# MAIN_CNTRL_v02.net
KiCad netlist of a schematic drawn in EAGLE
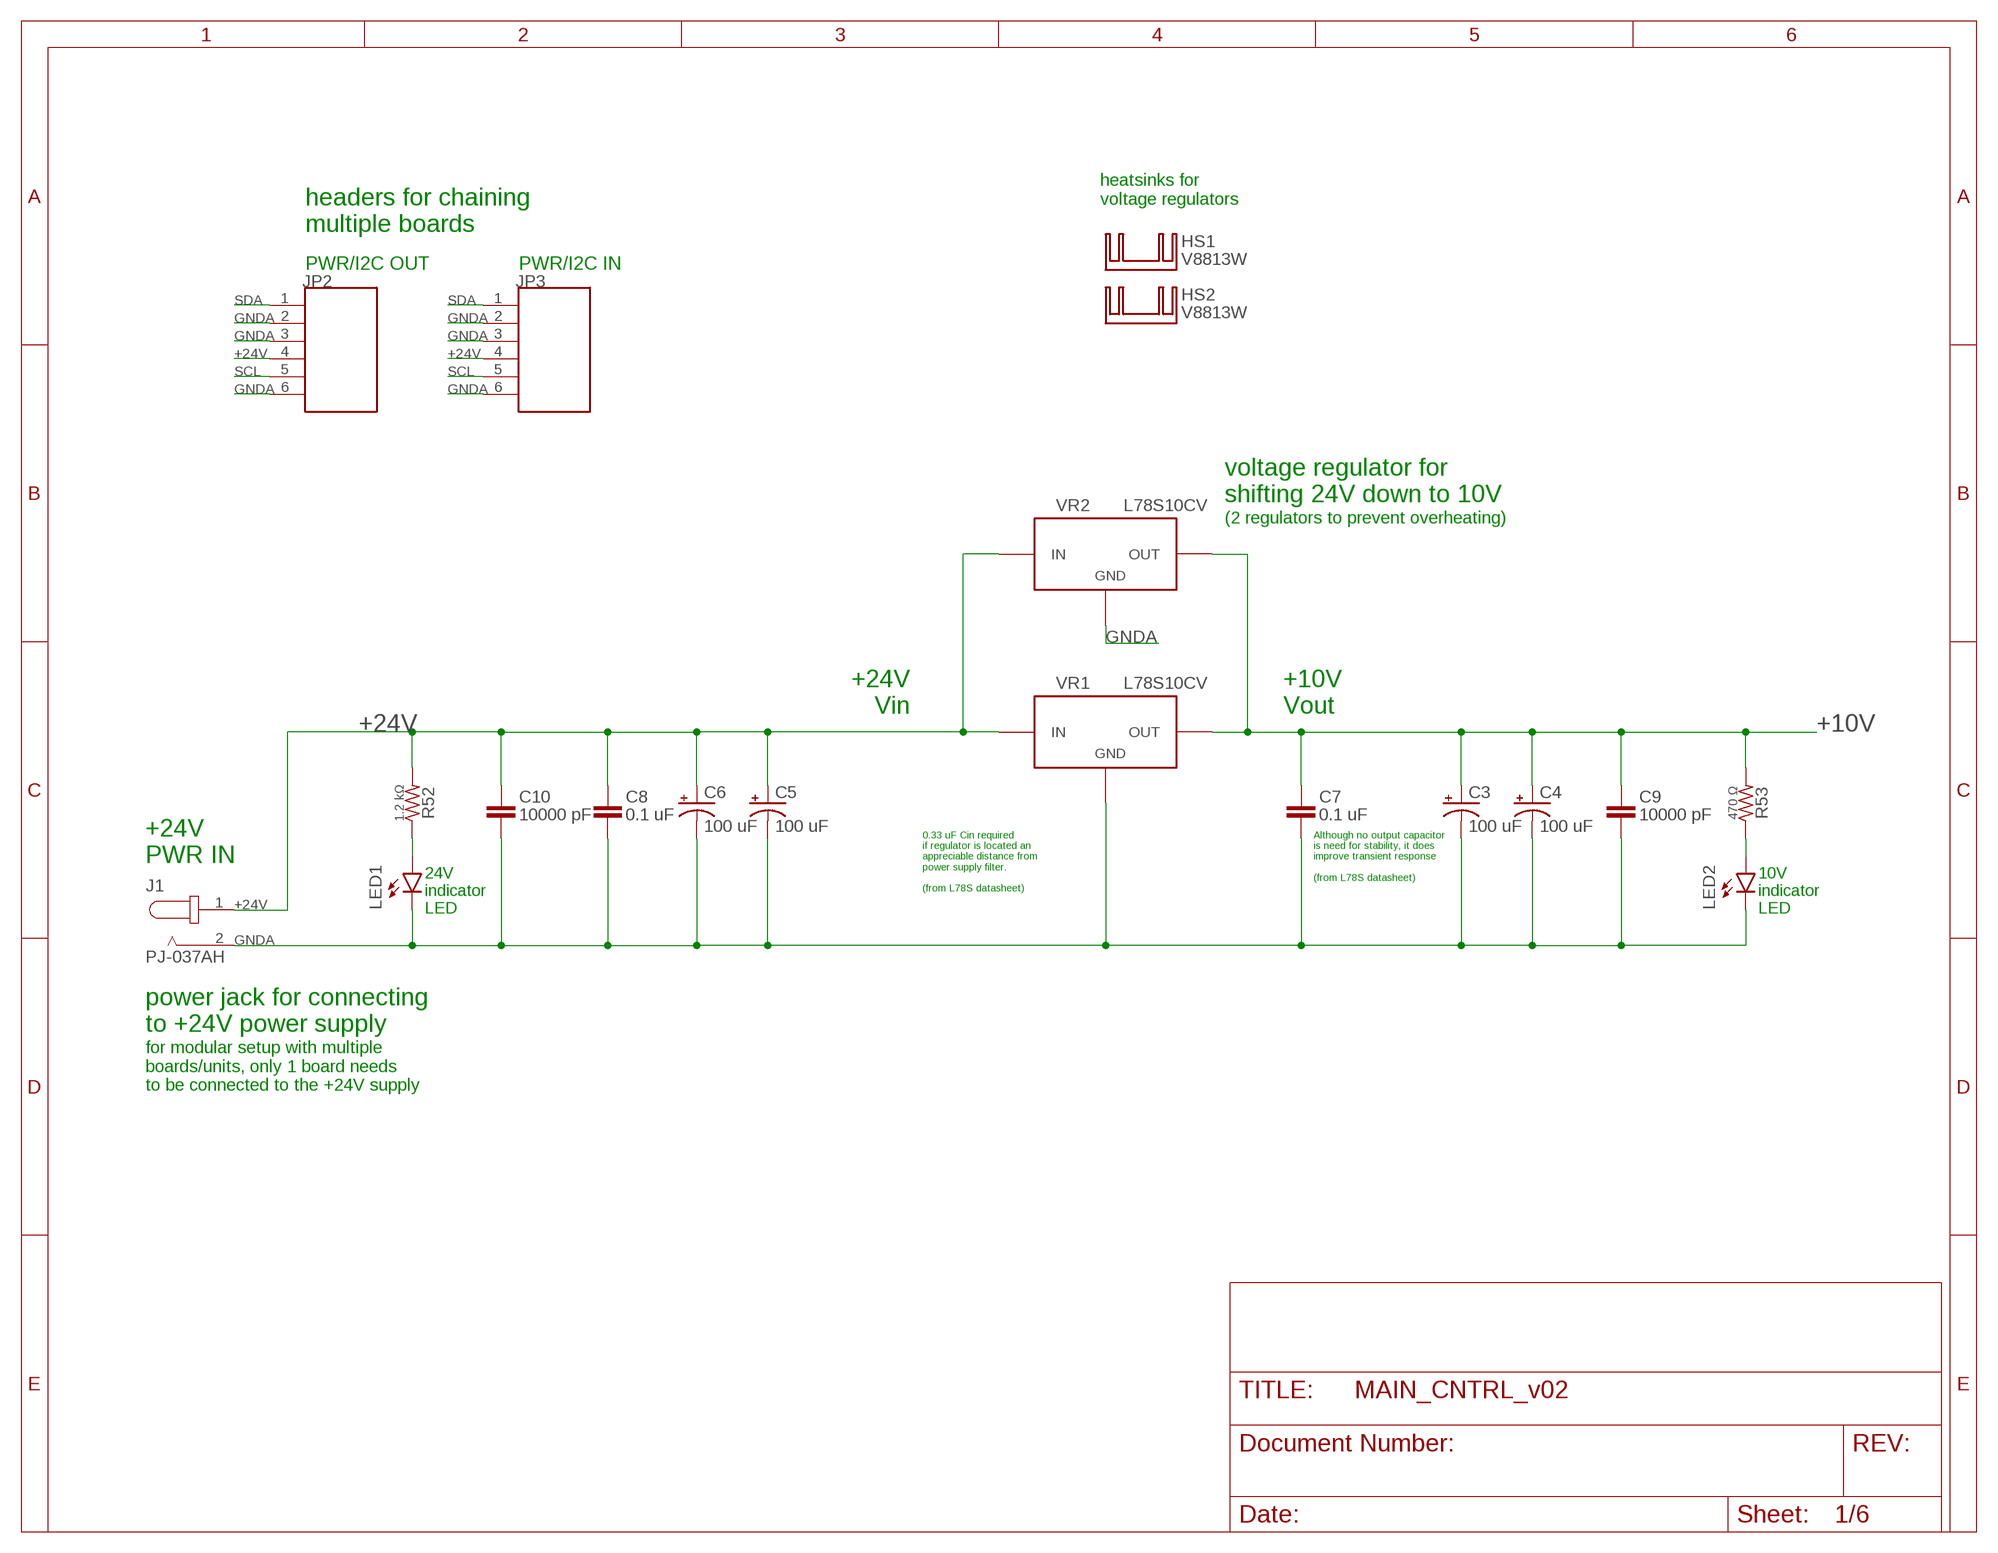
[diagram p0: schematic, sheet 1]
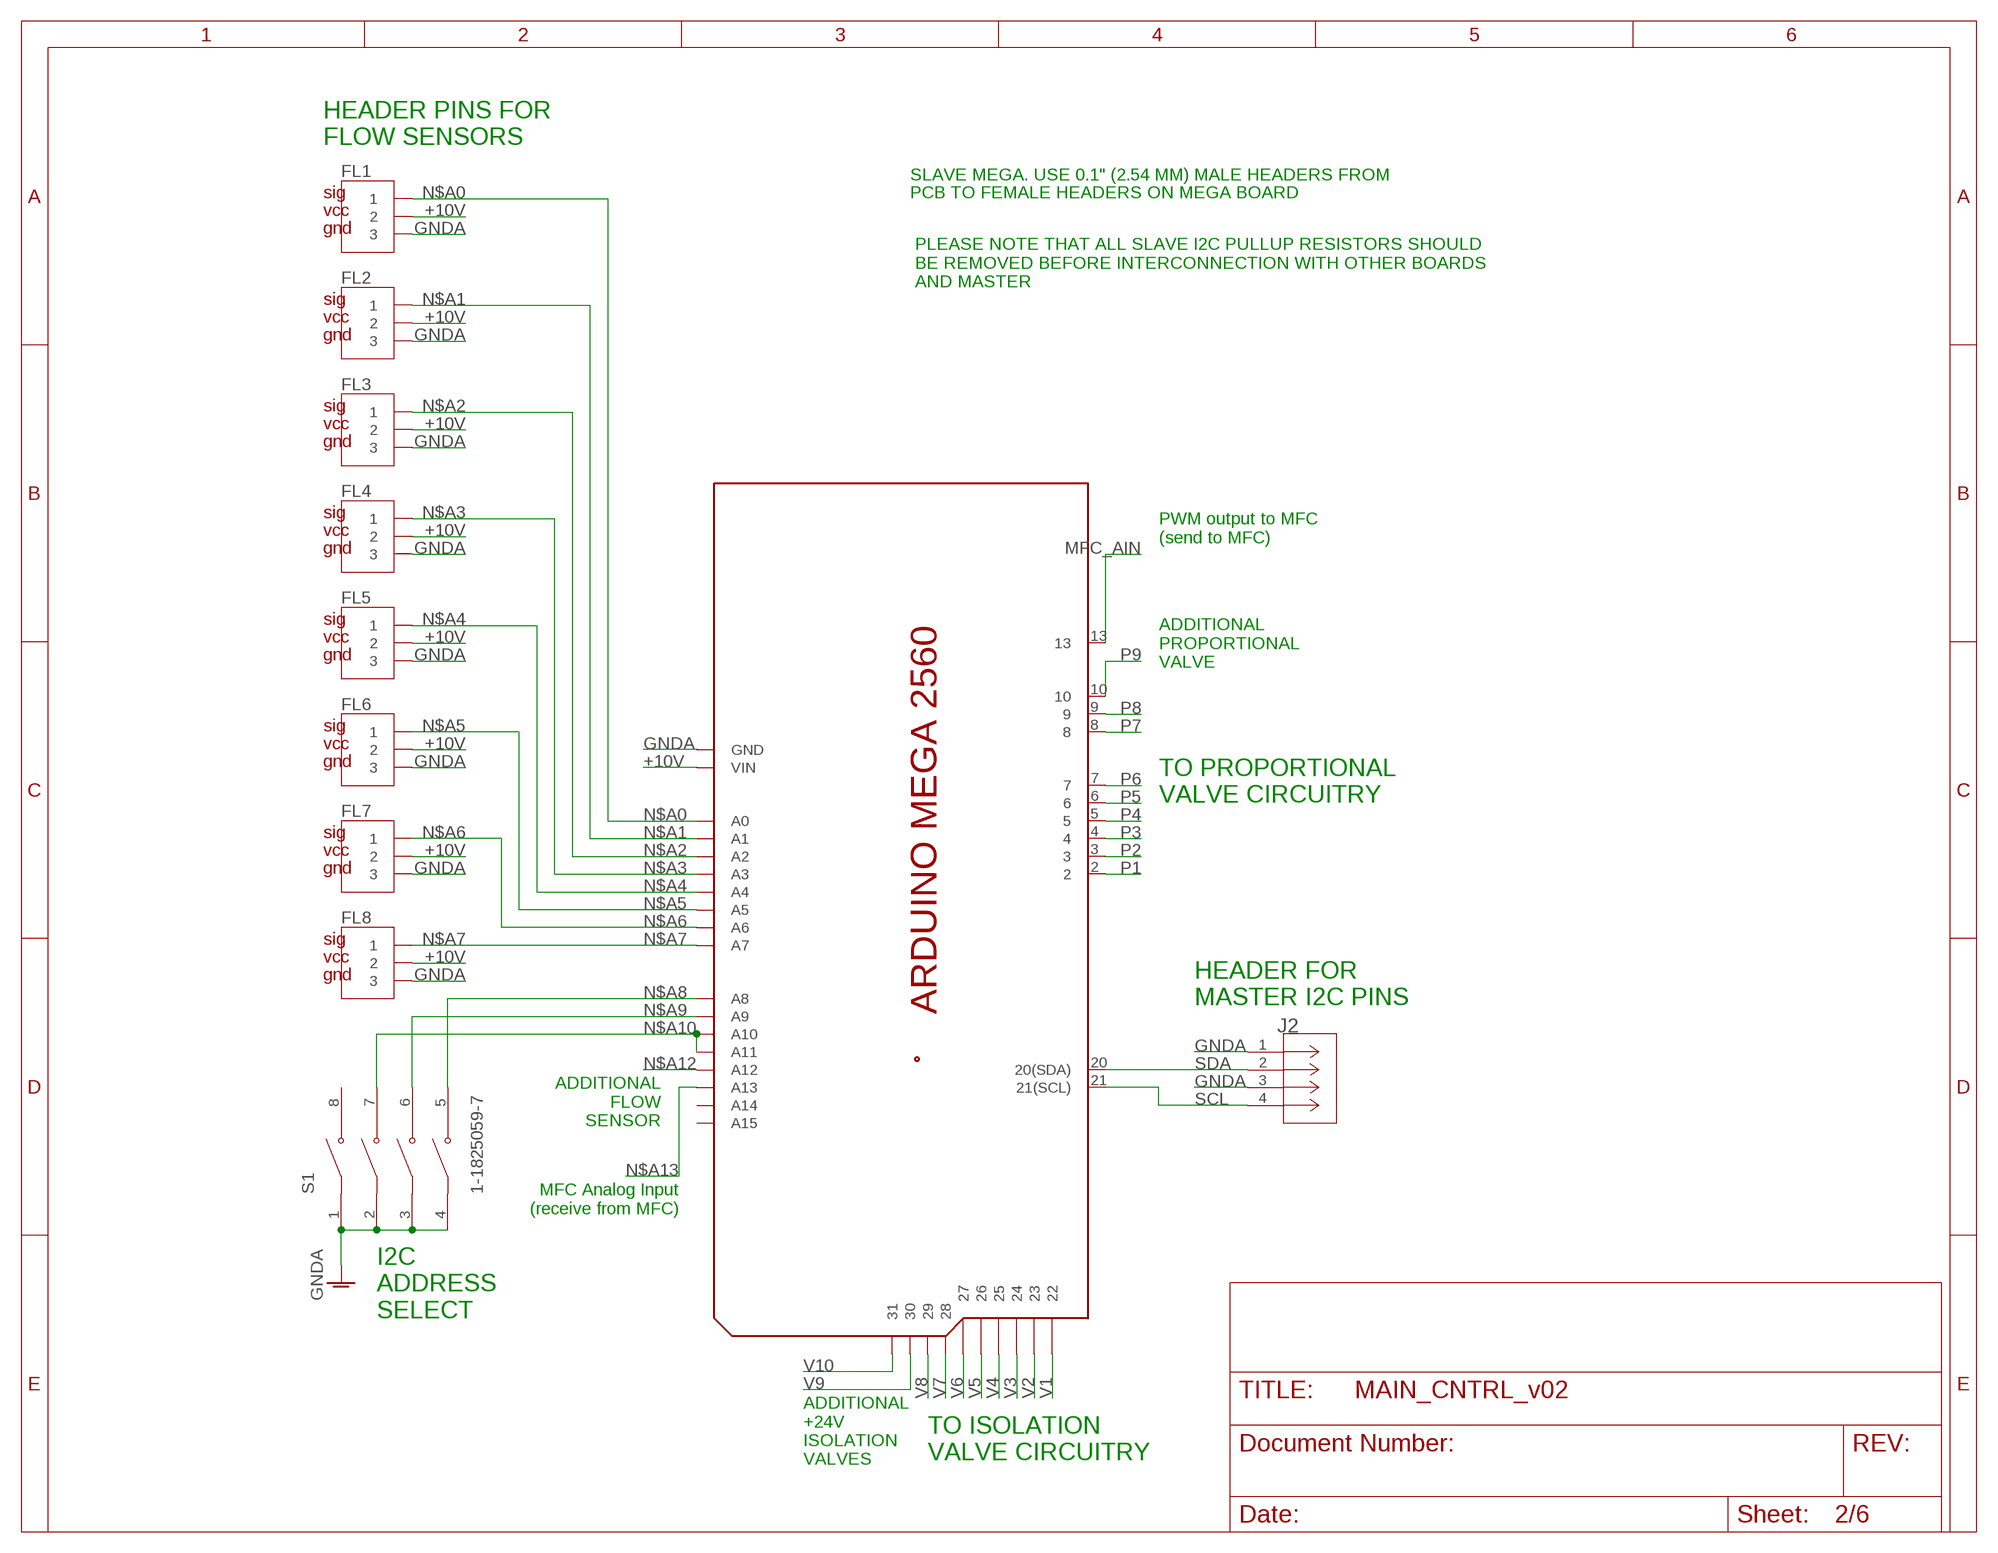
[diagram p1: schematic, sheet 2]
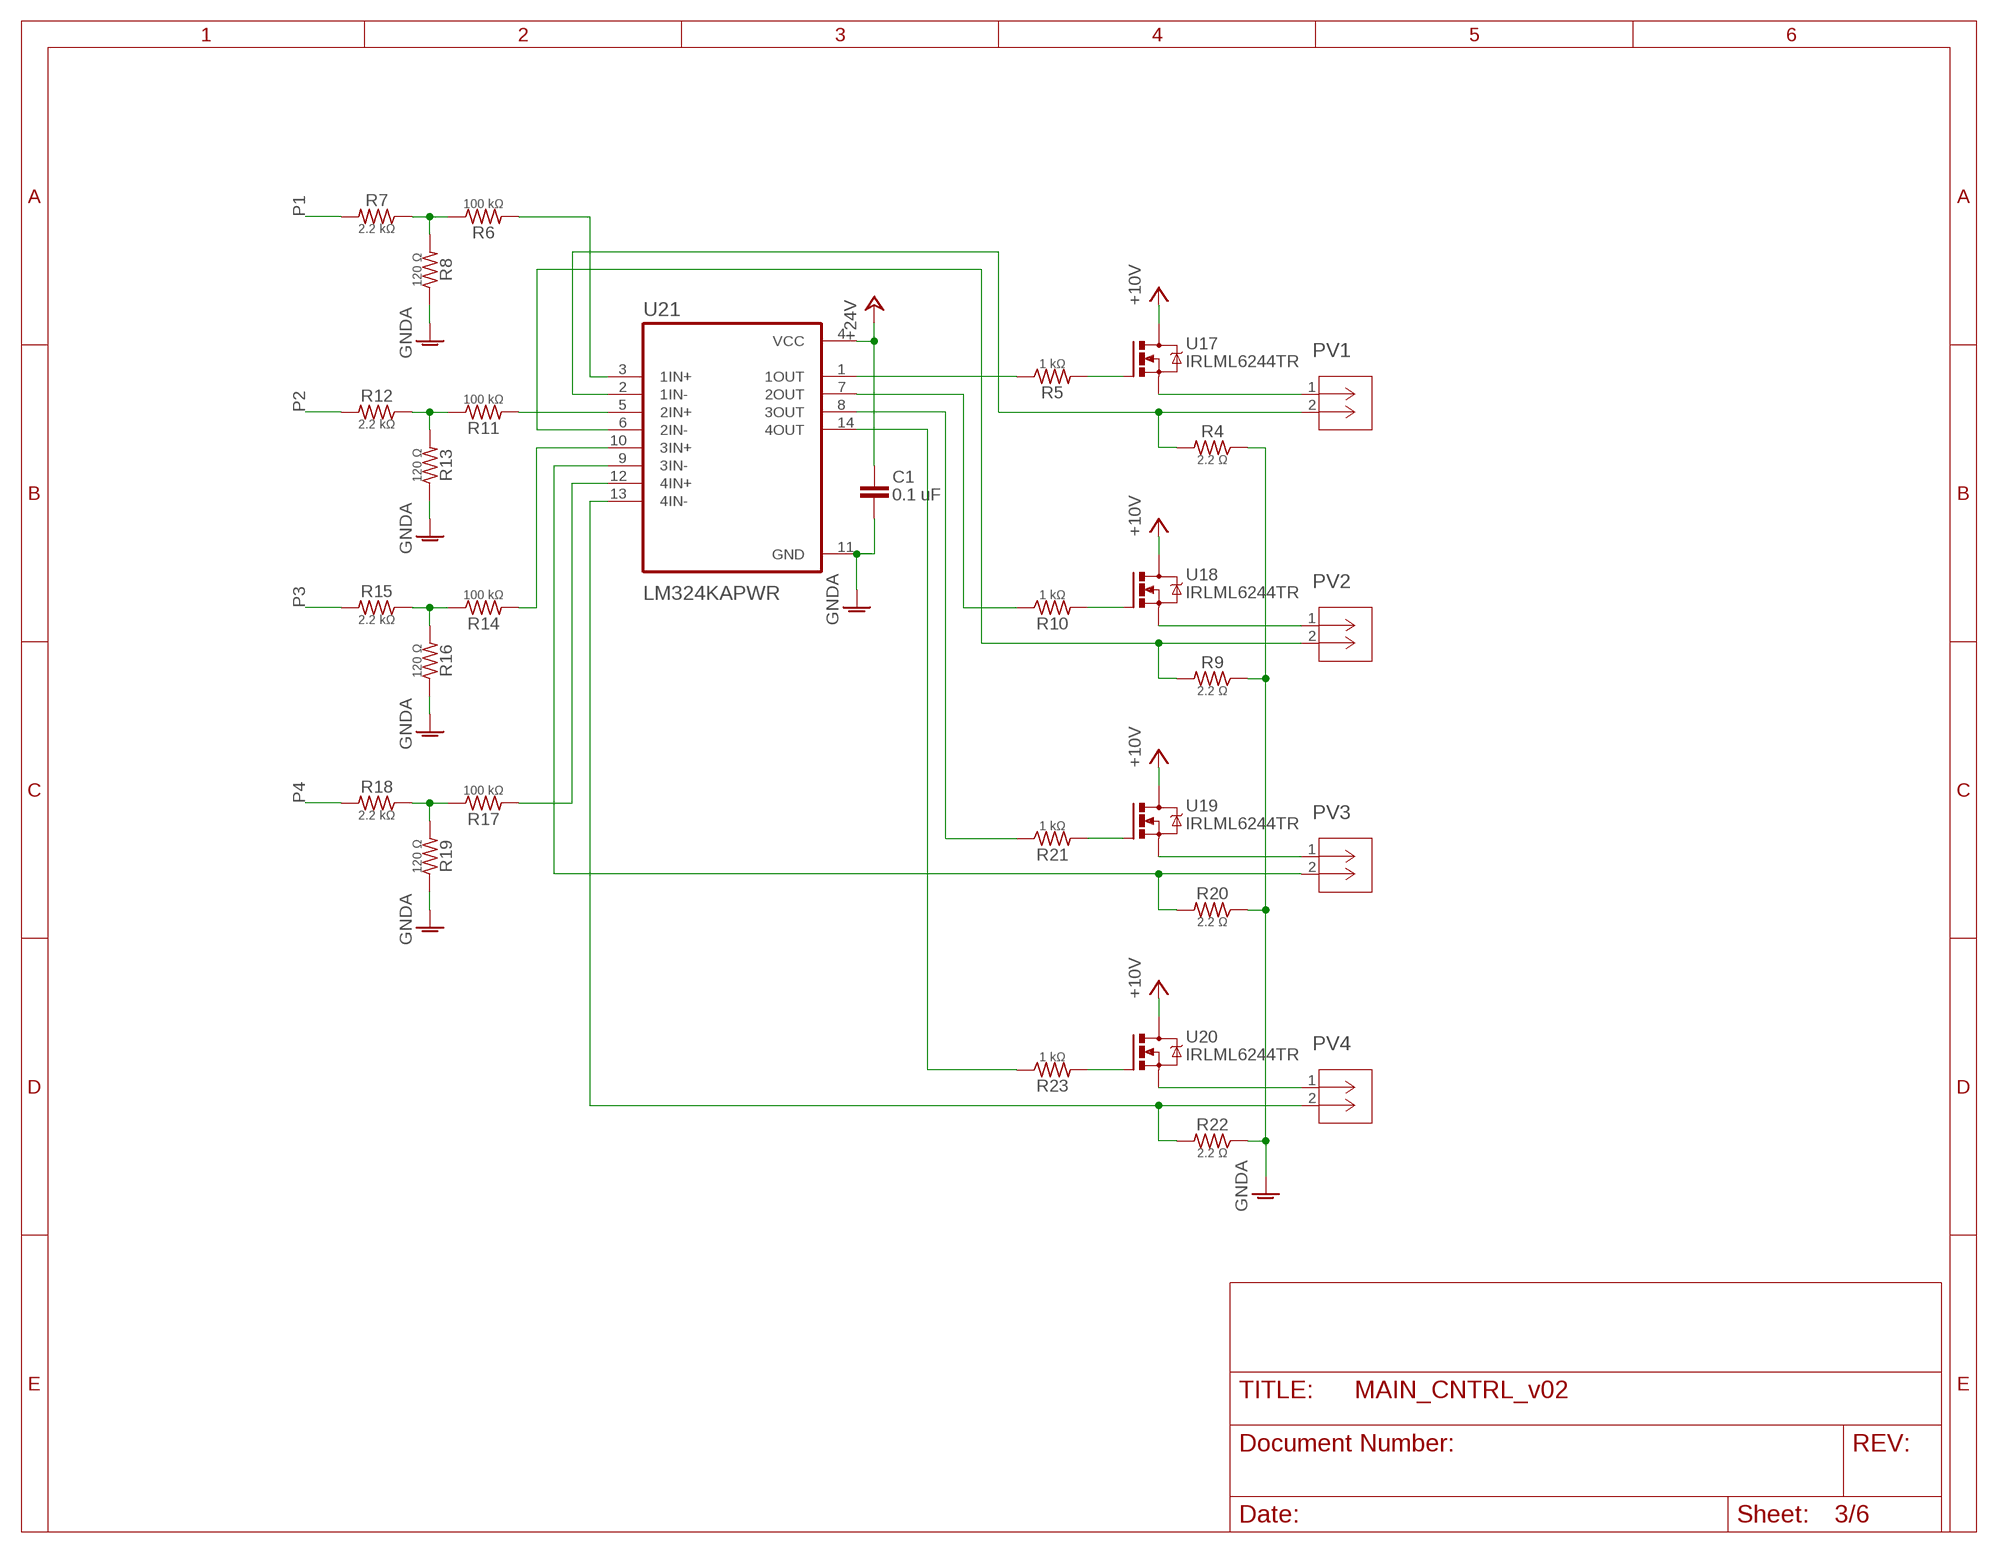
[diagram p2: schematic, sheet 3]
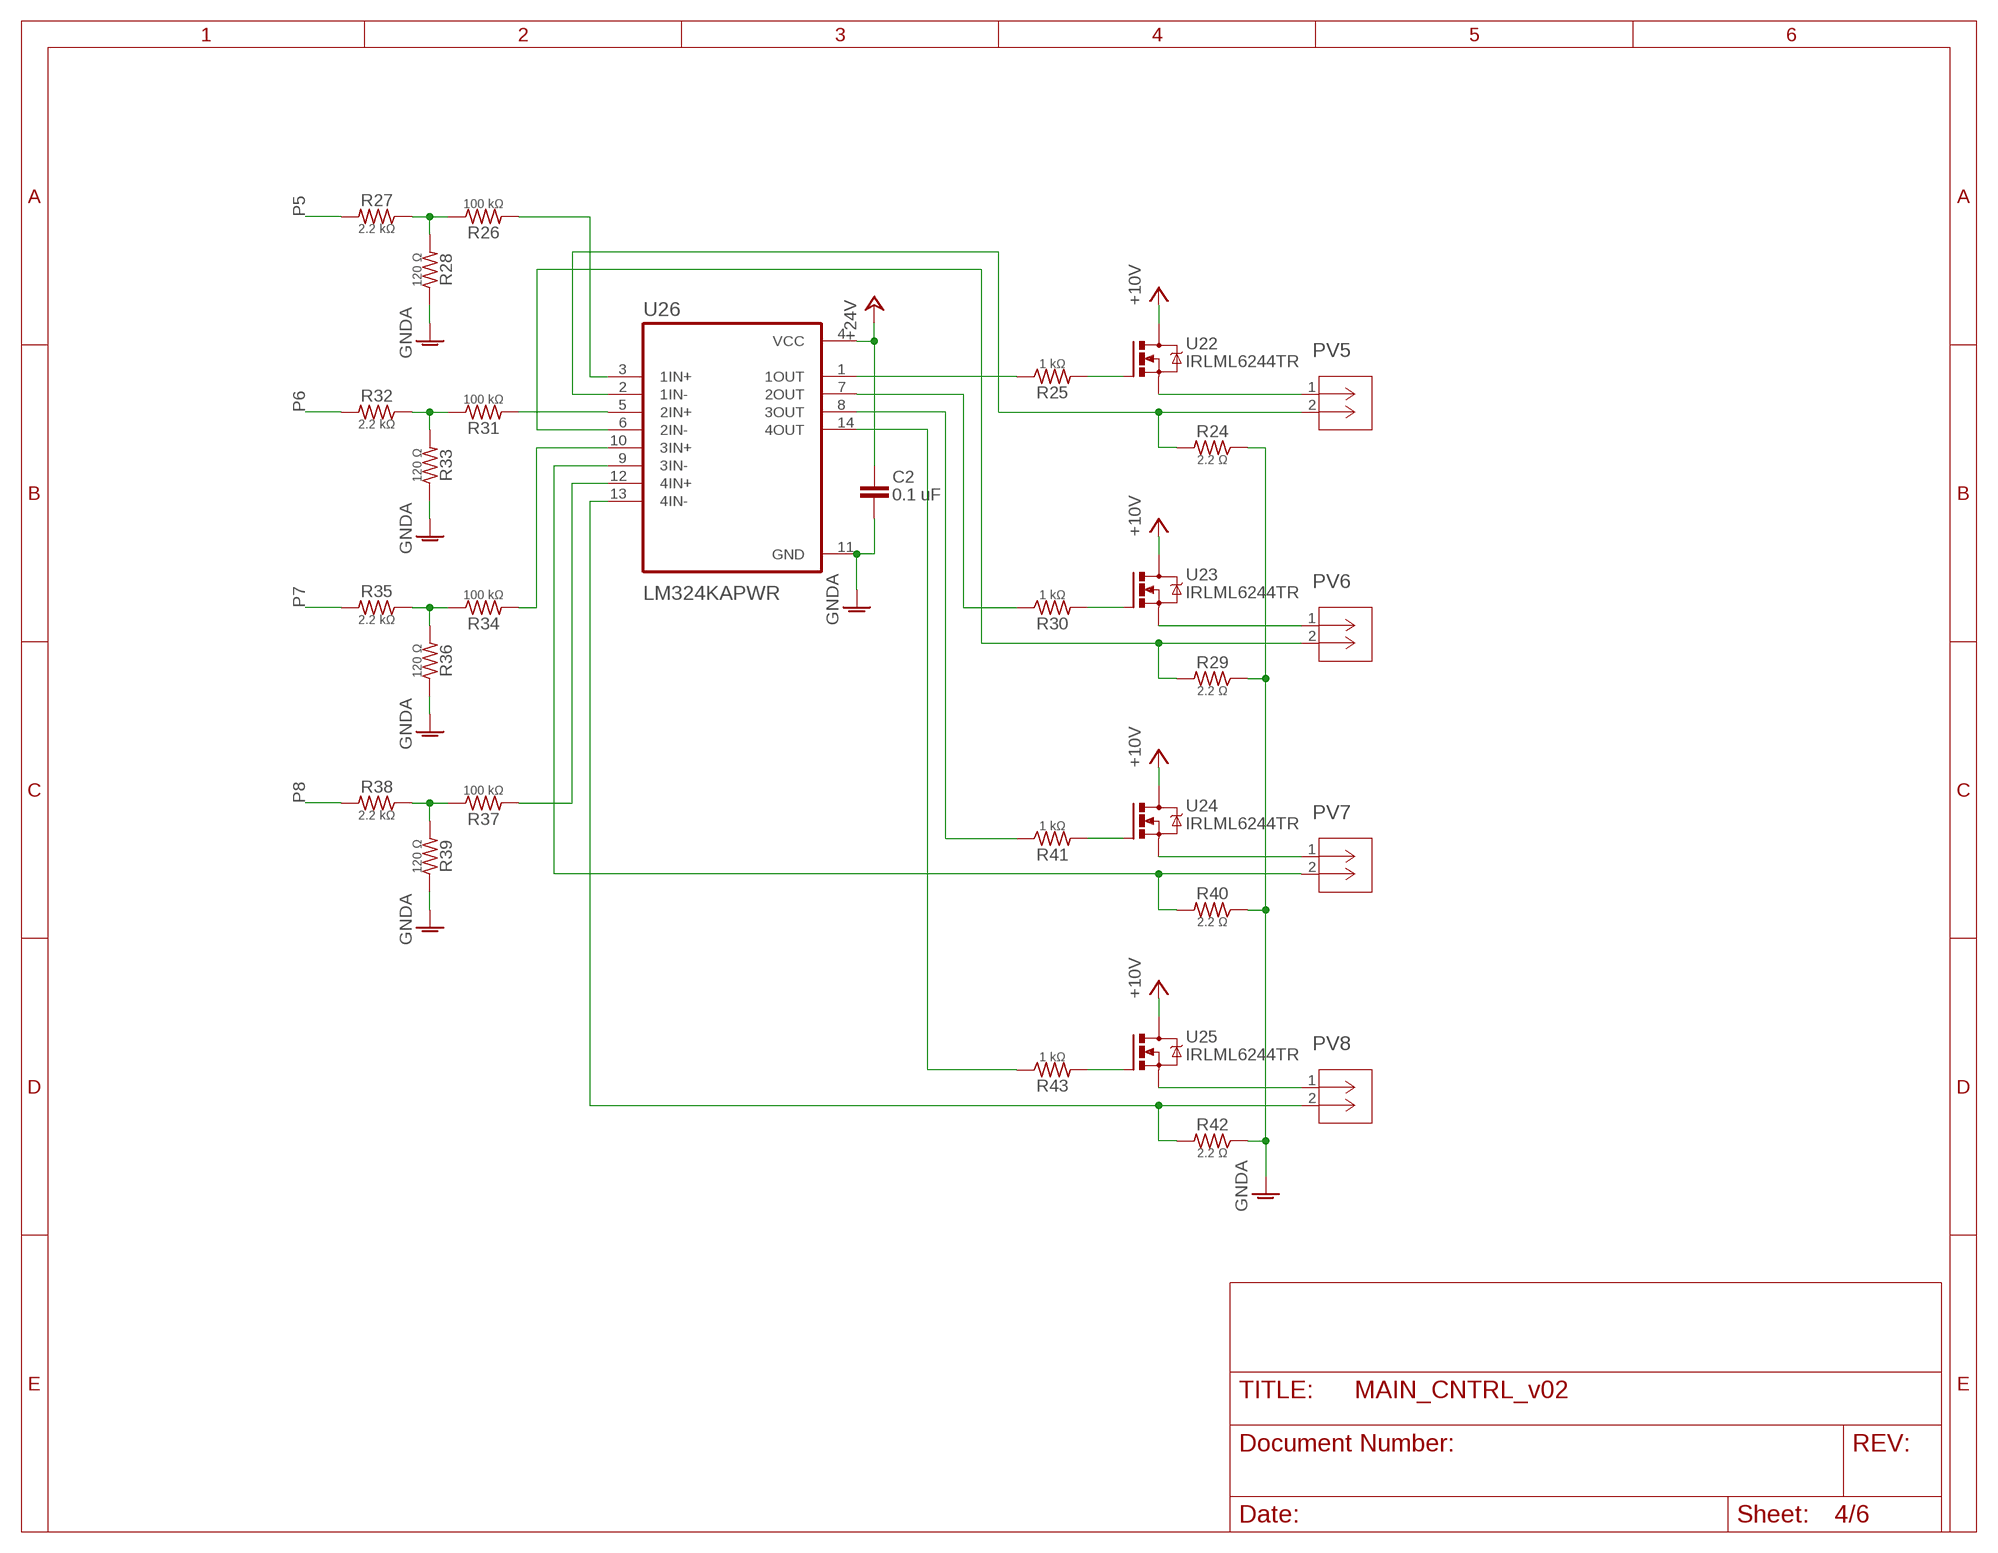
[diagram p3: schematic, sheet 4]
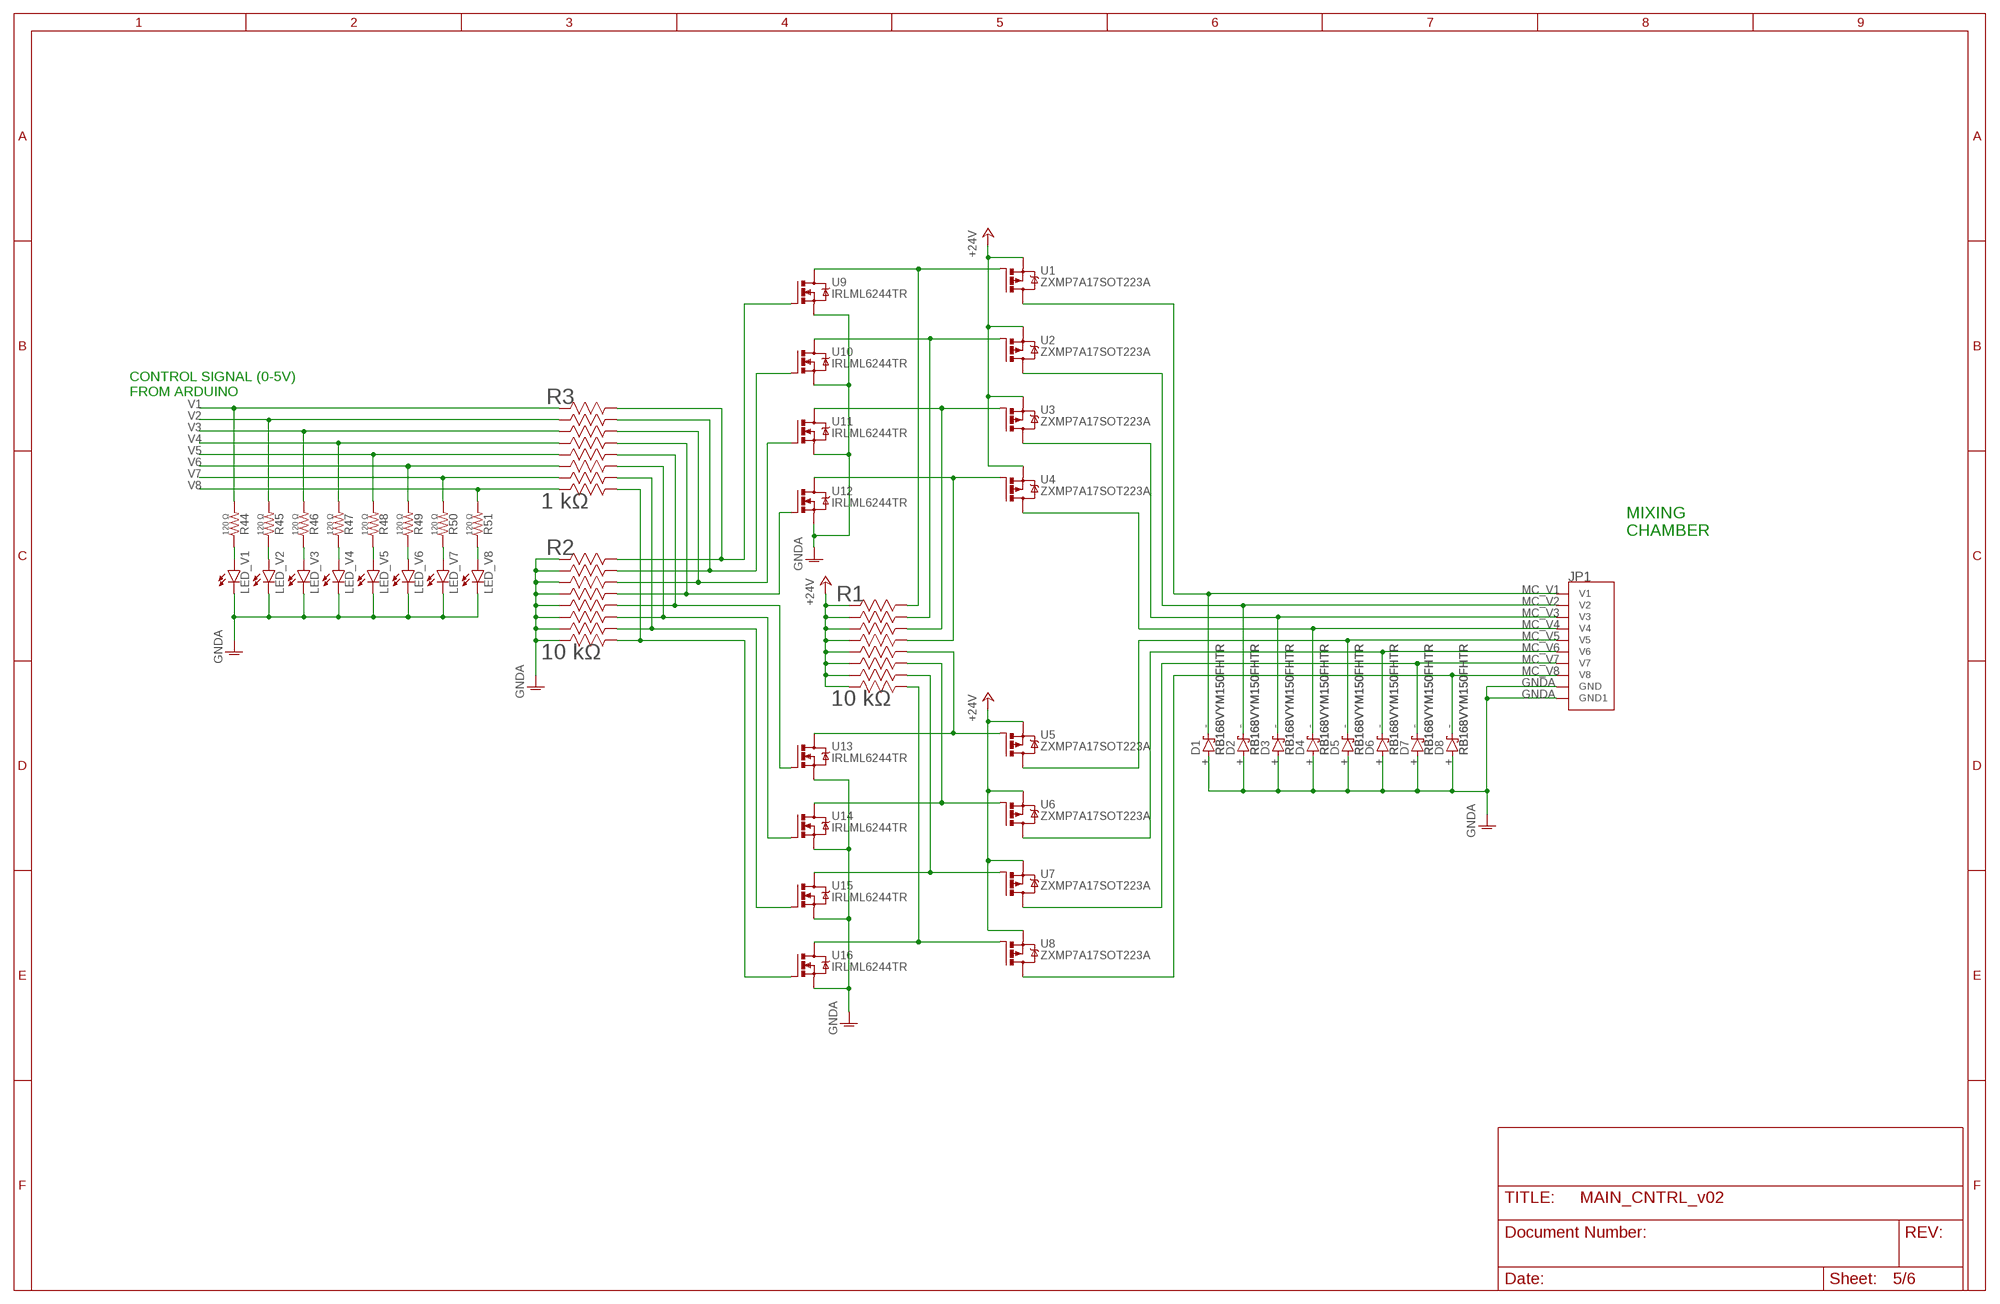
[diagram p4: schematic, sheet 5]
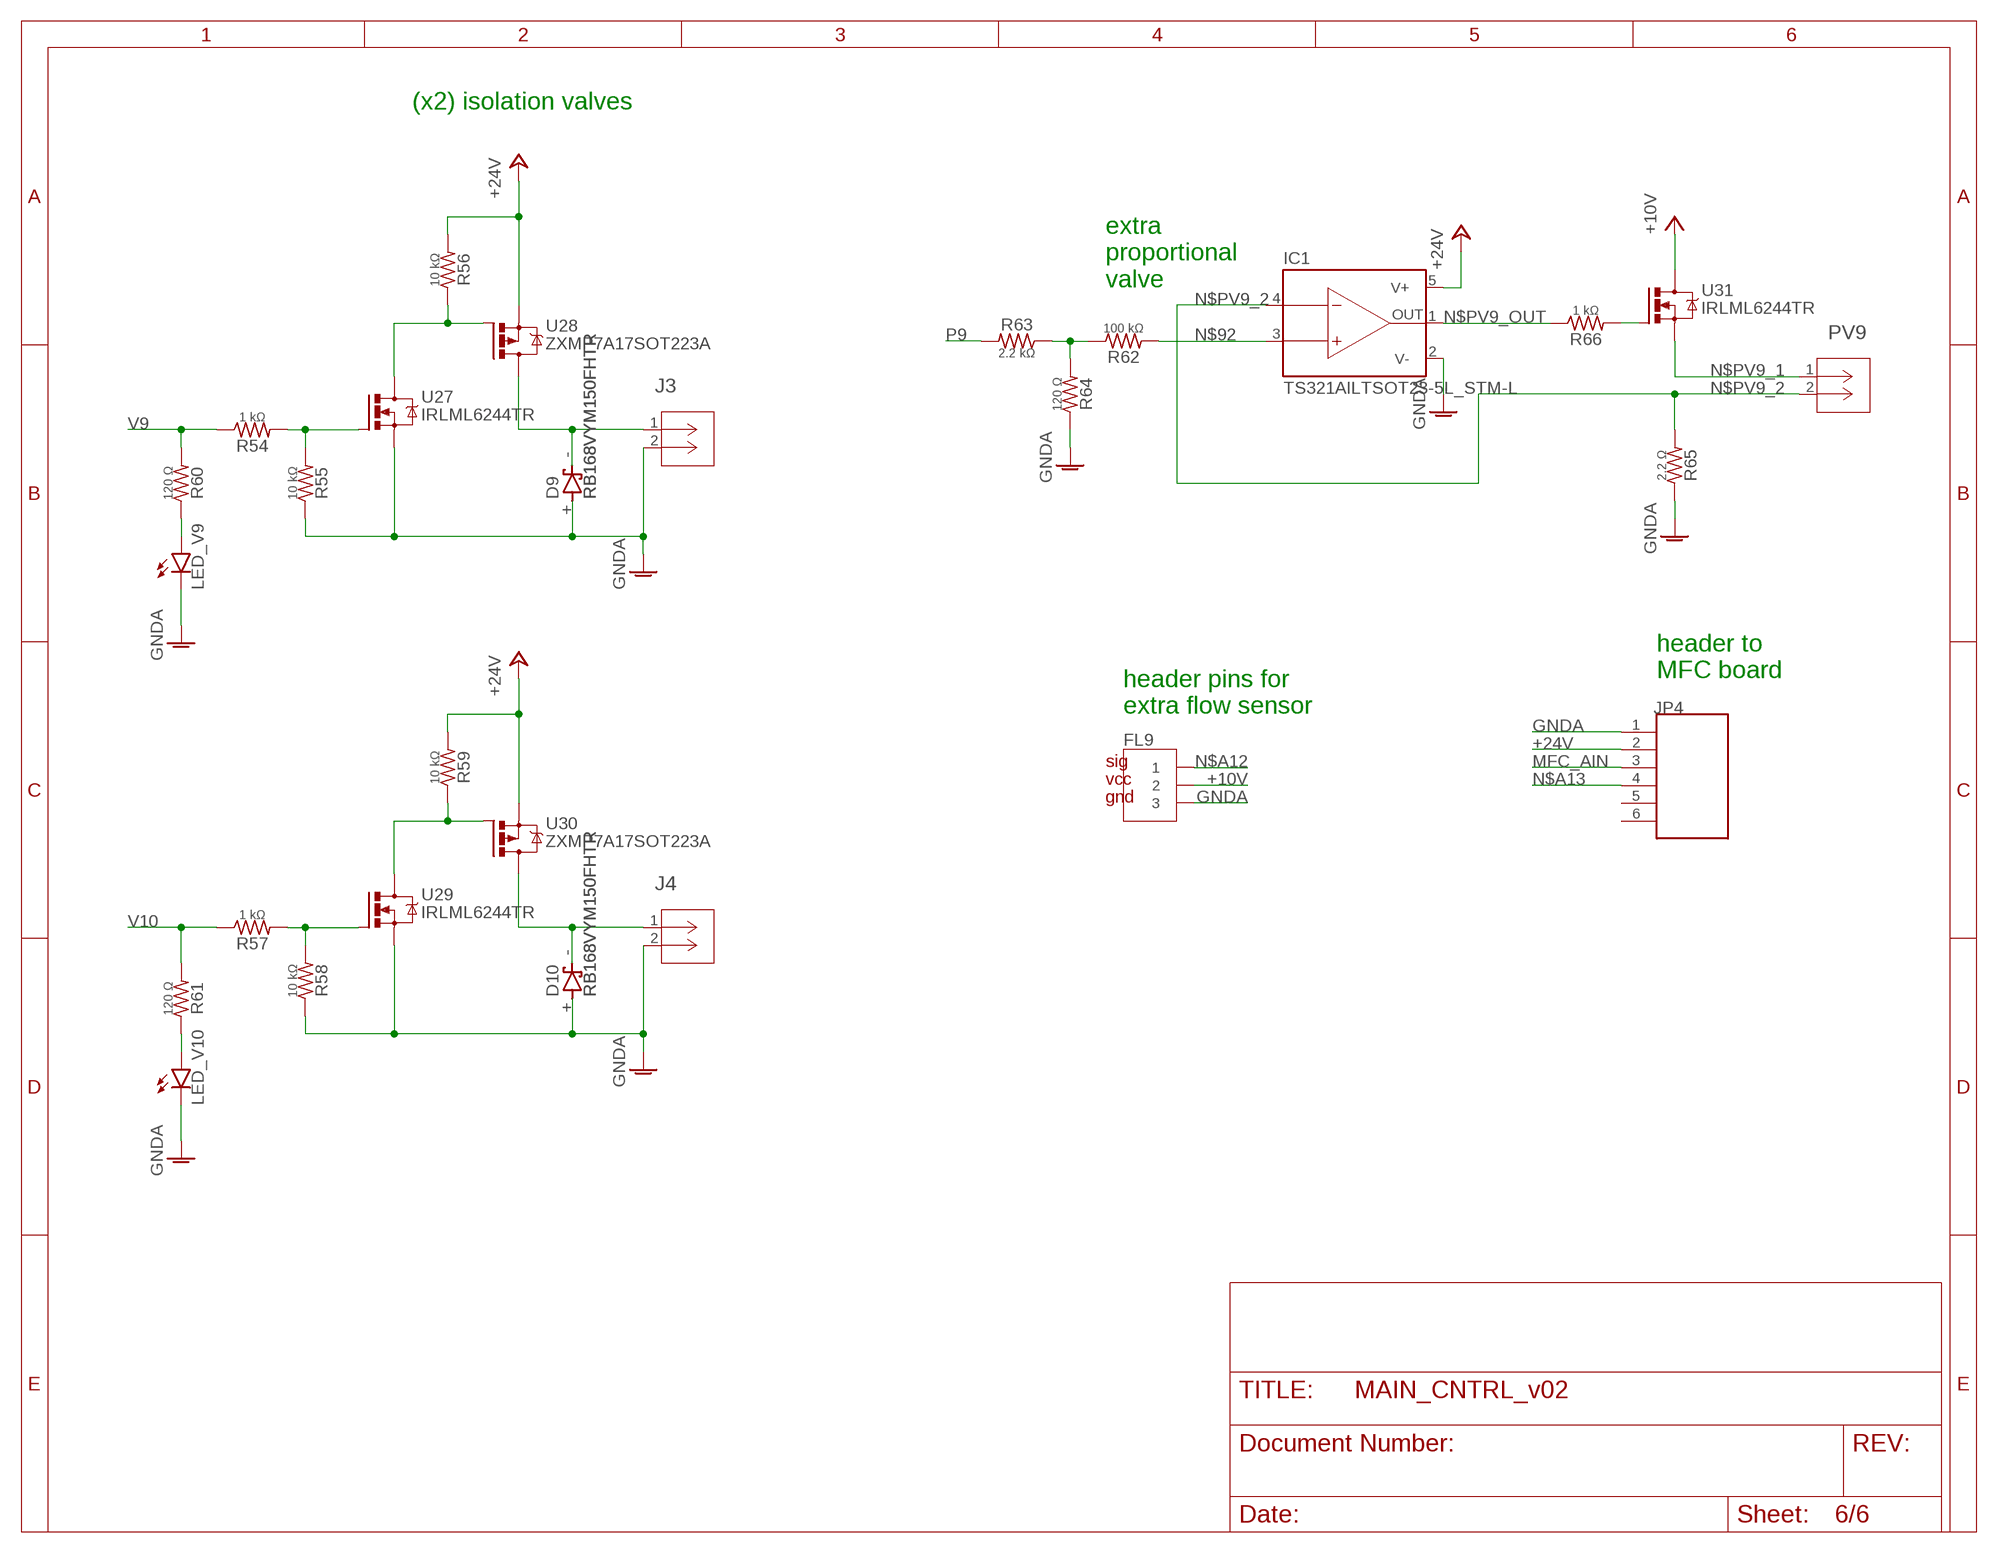
[diagram p5: schematic, sheet 6]

(export (version "E")
  (design (tool "Eeschema 10.0.6"))
  (components
    (comp (ref "D9")
      (value "RB168VYM150FHTR")
      (footprint "eagle-import:DIO_RB160VAM_ROM")
      (fields
        (field (name "DIGI-KEY_PART_NUMBER") "RB168VYM150FHCT-ND ")
        (field (name "MF") "ROHM Semiconductor")
        (field (name "COPYRIGHT") "Copyright (C) 2018 Accelerated Designs. All rights reserved")
      )
      (libsource (lib "eagle-import") (part "RB168VYM150FHTR"))
    )
    (comp (ref "D10")
      (value "RB168VYM150FHTR")
      (footprint "eagle-import:DIO_RB160VAM_ROM")
      (fields
        (field (name "DIGI-KEY_PART_NUMBER") "RB168VYM150FHCT-ND ")
        (field (name "MF") "ROHM Semiconductor")
        (field (name "COPYRIGHT") "Copyright (C) 2018 Accelerated Designs. All rights reserved")
      )
      (libsource (lib "eagle-import") (part "RB168VYM150FHTR"))
    )
    (comp (ref "FL9")
      (value "CONN_03_FL")
      (footprint "eagle-import:1X03_FL")
      (fields
        (field (name "DIGI-KEY_PART_NUMBER") "S7036-ND")
        (field (name "MF") "Sullins Connector Solutions")
        (field (name "MF_PART_NUMBER") "PPPC031LFBN-RC")
      )
      (libsource (lib "eagle-import") (part "CONN_03_FL"))
    )
    (comp (ref "IC1")
      (value "TS321AILTSOT23-5L_STM-L")
      (footprint "eagle-import:SOT23-5L_STM-L")
      (fields
        (field (name "DIGI-KEY_PART_NUMBER") "497-8093-1-ND")
        (field (name "MF") "STMicroelectronics")
        (field (name "MF_PART_NUMBER") "TS321AILT")
        (field (name "COPYRIGHT") "Copyright (C) 2022 Ultra Librarian. All rights reserved.")
      )
      (libsource (lib "eagle-import") (part "TS321AILTSOT23-5L_STM-L"))
    )
    (comp (ref "J3")
      (value "MOLEX_436500215")
      (footprint "eagle-import:MOLEX_2P_FOOTPRINT")
      (fields
        (field (name "DIGI-KEY_PART_NUMBER") "WM1917-ND")
        (field (name "MF") "Molex")
        (field (name "MF_PART_NUMBER") "0436500215")
      )
      (libsource (lib "eagle-import") (part "MOLEX_436500215"))
    )
    (comp (ref "J4")
      (value "MOLEX_436500215")
      (footprint "eagle-import:MOLEX_2P_FOOTPRINT")
      (fields
        (field (name "DIGI-KEY_PART_NUMBER") "WM1917-ND")
        (field (name "MF") "Molex")
        (field (name "MF_PART_NUMBER") "0436500215")
      )
      (libsource (lib "eagle-import") (part "MOLEX_436500215"))
    )
    (comp (ref "JP4")
      (value "CONN_06_HEADER")
      (footprint "eagle-import:CONN_6P_TE_1761681-1")
      (fields
        (field (name "DIGI-KEY_PART_NUMBER") "A122759-ND")
        (field (name "MF") "TE Connectivity AMP Connectors")
        (field (name "MF_PART_NUMBER") "1761681-1")
      )
      (libsource (lib "eagle-import") (part "CONN_06_HEADER"))
    )
    (comp (ref "LED_V9")
      (value "Blue LED")
      (footprint "eagle-import:LED_VISHAY_VLMX13XX")
      (fields
        (field (name "DIGI-KEY_PART_NUMBER") "VLMB1300-GS08CT-ND")
        (field (name "MF") "Vishay Semiconductor Opto Division")
        (field (name "MF_PART_NUMBER") "VLMB1300-GS08")
      )
      (libsource (lib "eagle-import") (part "LED_VLMB_1300"))
    )
    (comp (ref "LED_V10")
      (value "Blue LED")
      (footprint "eagle-import:LED_VISHAY_VLMX13XX")
      (fields
        (field (name "DIGI-KEY_PART_NUMBER") "VLMB1300-GS08CT-ND")
        (field (name "MF") "Vishay Semiconductor Opto Division")
        (field (name "MF_PART_NUMBER") "VLMB1300-GS08")
      )
      (libsource (lib "eagle-import") (part "LED_VLMB_1300"))
    )
    (comp (ref "PV9")
      (value "MOLEX_436500215PVALVES")
      (footprint "eagle-import:MOLEX_2P_PVALVES")
      (libsource (lib "eagle-import") (part "MOLEX_436500215PVALVES"))
    )
    (comp (ref "R54")
      (value "1 kΩ")
      (footprint "eagle-import:RES_ERJPA3F1001V")
      (fields
        (field (name "DIGI-KEY_PART_NUMBER") "P1.0KBYCT-ND")
        (field (name "MF") "Panasonic")
        (field (name "MF_PART_NUMBER") "ERJPA3F1001V")
      )
      (libsource (lib "eagle-import") (part "ERJPA3F1001V"))
    )
    (comp (ref "R55")
      (value "10 kΩ")
      (footprint "eagle-import:RES_ERJPA3F1001V")
      (fields
        (field (name "DIGI-KEY_PART_NUMBER") "P10KBYCT-ND")
        (field (name "MF") "Panasonic")
        (field (name "MF_PART_NUMBER") "ERJ-PA3F1002V")
      )
      (libsource (lib "eagle-import") (part "ERJ-PA3F1002V"))
    )
    (comp (ref "R56")
      (value "10 kΩ")
      (footprint "eagle-import:RES_ERJPA3F1001V")
      (fields
        (field (name "DIGI-KEY_PART_NUMBER") "P10KBYCT-ND")
        (field (name "MF") "Panasonic")
        (field (name "MF_PART_NUMBER") "ERJ-PA3F1002V")
      )
      (libsource (lib "eagle-import") (part "ERJ-PA3F1002V"))
    )
    (comp (ref "R57")
      (value "1 kΩ")
      (footprint "eagle-import:RES_ERJPA3F1001V")
      (fields
        (field (name "DIGI-KEY_PART_NUMBER") "P1.0KBYCT-ND")
        (field (name "MF") "Panasonic")
        (field (name "MF_PART_NUMBER") "ERJPA3F1001V")
      )
      (libsource (lib "eagle-import") (part "ERJPA3F1001V"))
    )
    (comp (ref "R58")
      (value "10 kΩ")
      (footprint "eagle-import:RES_ERJPA3F1001V")
      (fields
        (field (name "DIGI-KEY_PART_NUMBER") "P10KBYCT-ND")
        (field (name "MF") "Panasonic")
        (field (name "MF_PART_NUMBER") "ERJ-PA3F1002V")
      )
      (libsource (lib "eagle-import") (part "ERJ-PA3F1002V"))
    )
    (comp (ref "R59")
      (value "10 kΩ")
      (footprint "eagle-import:RES_ERJPA3F1001V")
      (fields
        (field (name "DIGI-KEY_PART_NUMBER") "P10KBYCT-ND")
        (field (name "MF") "Panasonic")
        (field (name "MF_PART_NUMBER") "ERJ-PA3F1002V")
      )
      (libsource (lib "eagle-import") (part "ERJ-PA3F1002V"))
    )
    (comp (ref "R60")
      (value "120 Ω")
      (footprint "eagle-import:RCS0603_REFLOW")
      (fields
        (field (name "DIGI-KEY_PART_NUMBER") "541-10426-1-ND")
        (field (name "MF") "Vishay")
        (field (name "MF_PART_NUMBER") "RCS0603120RFKEA")
      )
      (libsource (lib "eagle-import") (part "RCS0603120RFKEA"))
    )
    (comp (ref "R61")
      (value "120 Ω")
      (footprint "eagle-import:RCS0603_REFLOW")
      (fields
        (field (name "DIGI-KEY_PART_NUMBER") "541-10426-1-ND")
        (field (name "MF") "Vishay")
        (field (name "MF_PART_NUMBER") "RCS0603120RFKEA")
      )
      (libsource (lib "eagle-import") (part "RCS0603120RFKEA"))
    )
    (comp (ref "R62")
      (value "100 kΩ")
      (footprint "eagle-import:RESC1608X55N")
      (fields
        (field (name "DIGI-KEY_PART_NUMBER") "YAG5821CT-ND")
        (field (name "MF") "Yageo")
        (field (name "MF_PART_NUMBER") "SR0603FR-7T100KL")
      )
      (libsource (lib "eagle-import") (part "SR0603FR-7T100KL"))
    )
    (comp (ref "R63")
      (value "2.2 kΩ")
      (footprint "eagle-import:RESC1608X55N")
      (fields
        (field (name "DIGI-KEY_PART_NUMBER") "YAG5834CT-ND")
        (field (name "MF") "Yageo")
        (field (name "MF_PART_NUMBER") "SR0603FR-7T2K2L")
      )
      (libsource (lib "eagle-import") (part "SR0603FR-7T2K2L"))
    )
    (comp (ref "R64")
      (value "120 Ω")
      (footprint "eagle-import:RCS0603_REFLOW")
      (fields
        (field (name "DIGI-KEY_PART_NUMBER") "541-10426-1-ND")
        (field (name "MF") "Vishay")
        (field (name "MF_PART_NUMBER") "RCS0603120RFKEA")
      )
      (libsource (lib "eagle-import") (part "RCS0603120RFKEA"))
    )
    (comp (ref "R65")
      (value "2.2 Ω")
      (footprint "eagle-import:CRCW1206_E3_REFLOW")
      (fields
        (field (name "DIGI-KEY_PART_NUMBER") "541-2.20FFCT-ND")
        (field (name "MF") "Vishay Dale")
        (field (name "MF_PART_NUMBER") "CRCW12062R20FKEA")
      )
      (libsource (lib "eagle-import") (part "CRCW12062R20FKEA"))
    )
    (comp (ref "R66")
      (value "1 kΩ")
      (footprint "eagle-import:RES_ERJPA3F1001V")
      (fields
        (field (name "DIGI-KEY_PART_NUMBER") "P1.0KBYCT-ND")
        (field (name "MF") "Panasonic")
        (field (name "MF_PART_NUMBER") "ERJPA3F1001V")
      )
      (libsource (lib "eagle-import") (part "ERJPA3F1001V"))
    )
    (comp (ref "U27")
      (value "IRLML6244TR")
      (footprint "eagle-import:SOT23")
      (fields
        (field (name "DIGI-KEY_PART_NUMBER") "IRLML6244TRPBFCT-ND")
        (field (name "MF") "Infineon Technologies")
        (field (name "MF_PART_NUMBER") "IRLML6244TRPBF")
      )
      (libsource (lib "eagle-import") (part "IRLML6244TR"))
    )
    (comp (ref "U28")
      (value "ZXMP7A17SOT223A")
      (footprint "eagle-import:SOT223")
      (fields
        (field (name "DIGI-KEY_PART_NUMBER") "ZXMP7A17GQTADICT-ND")
        (field (name "MF") "Diodes Incorporated")
        (field (name "MF_PART_NUMBER") "ZXMP7A17GQTA")
      )
      (libsource (lib "eagle-import") (part "ZXMP7A17SOT223A"))
    )
    (comp (ref "U29")
      (value "IRLML6244TR")
      (footprint "eagle-import:SOT23")
      (fields
        (field (name "DIGI-KEY_PART_NUMBER") "IRLML6244TRPBFCT-ND")
        (field (name "MF") "Infineon Technologies")
        (field (name "MF_PART_NUMBER") "IRLML6244TRPBF")
      )
      (libsource (lib "eagle-import") (part "IRLML6244TR"))
    )
    (comp (ref "U30")
      (value "ZXMP7A17SOT223A")
      (footprint "eagle-import:SOT223")
      (fields
        (field (name "DIGI-KEY_PART_NUMBER") "ZXMP7A17GQTADICT-ND")
        (field (name "MF") "Diodes Incorporated")
        (field (name "MF_PART_NUMBER") "ZXMP7A17GQTA")
      )
      (libsource (lib "eagle-import") (part "ZXMP7A17SOT223A"))
    )
    (comp (ref "U31")
      (value "IRLML6244TR")
      (footprint "eagle-import:SOT23")
      (fields
        (field (name "DIGI-KEY_PART_NUMBER") "IRLML6244TRPBFCT-ND")
        (field (name "MF") "Infineon Technologies")
        (field (name "MF_PART_NUMBER") "IRLML6244TRPBF")
      )
      (libsource (lib "eagle-import") (part "IRLML6244TR"))
    )
    (comp (ref "D1")
      (value "RB168VYM150FHTR")
      (footprint "eagle-import:DIO_RB160VAM_ROM")
      (fields
        (field (name "DIGI-KEY_PART_NUMBER") "RB168VYM150FHCT-ND ")
        (field (name "MF") "ROHM Semiconductor")
        (field (name "COPYRIGHT") "Copyright (C) 2018 Accelerated Designs. All rights reserved")
      )
      (libsource (lib "eagle-import") (part "RB168VYM150FHTR"))
    )
    (comp (ref "D2")
      (value "RB168VYM150FHTR")
      (footprint "eagle-import:DIO_RB160VAM_ROM")
      (fields
        (field (name "DIGI-KEY_PART_NUMBER") "RB168VYM150FHCT-ND ")
        (field (name "MF") "ROHM Semiconductor")
        (field (name "COPYRIGHT") "Copyright (C) 2018 Accelerated Designs. All rights reserved")
      )
      (libsource (lib "eagle-import") (part "RB168VYM150FHTR"))
    )
    (comp (ref "D3")
      (value "RB168VYM150FHTR")
      (footprint "eagle-import:DIO_RB160VAM_ROM")
      (fields
        (field (name "DIGI-KEY_PART_NUMBER") "RB168VYM150FHCT-ND ")
        (field (name "MF") "ROHM Semiconductor")
        (field (name "COPYRIGHT") "Copyright (C) 2018 Accelerated Designs. All rights reserved")
      )
      (libsource (lib "eagle-import") (part "RB168VYM150FHTR"))
    )
    (comp (ref "D4")
      (value "RB168VYM150FHTR")
      (footprint "eagle-import:DIO_RB160VAM_ROM")
      (fields
        (field (name "DIGI-KEY_PART_NUMBER") "RB168VYM150FHCT-ND ")
        (field (name "MF") "ROHM Semiconductor")
        (field (name "COPYRIGHT") "Copyright (C) 2018 Accelerated Designs. All rights reserved")
      )
      (libsource (lib "eagle-import") (part "RB168VYM150FHTR"))
    )
    (comp (ref "D5")
      (value "RB168VYM150FHTR")
      (footprint "eagle-import:DIO_RB160VAM_ROM")
      (fields
        (field (name "DIGI-KEY_PART_NUMBER") "RB168VYM150FHCT-ND ")
        (field (name "MF") "ROHM Semiconductor")
        (field (name "COPYRIGHT") "Copyright (C) 2018 Accelerated Designs. All rights reserved")
      )
      (libsource (lib "eagle-import") (part "RB168VYM150FHTR"))
    )
    (comp (ref "D6")
      (value "RB168VYM150FHTR")
      (footprint "eagle-import:DIO_RB160VAM_ROM")
      (fields
        (field (name "DIGI-KEY_PART_NUMBER") "RB168VYM150FHCT-ND ")
        (field (name "MF") "ROHM Semiconductor")
        (field (name "COPYRIGHT") "Copyright (C) 2018 Accelerated Designs. All rights reserved")
      )
      (libsource (lib "eagle-import") (part "RB168VYM150FHTR"))
    )
    (comp (ref "D7")
      (value "RB168VYM150FHTR")
      (footprint "eagle-import:DIO_RB160VAM_ROM")
      (fields
        (field (name "DIGI-KEY_PART_NUMBER") "RB168VYM150FHCT-ND ")
        (field (name "MF") "ROHM Semiconductor")
        (field (name "COPYRIGHT") "Copyright (C) 2018 Accelerated Designs. All rights reserved")
      )
      (libsource (lib "eagle-import") (part "RB168VYM150FHTR"))
    )
    (comp (ref "D8")
      (value "RB168VYM150FHTR")
      (footprint "eagle-import:DIO_RB160VAM_ROM")
      (fields
        (field (name "DIGI-KEY_PART_NUMBER") "RB168VYM150FHCT-ND ")
        (field (name "MF") "ROHM Semiconductor")
        (field (name "COPYRIGHT") "Copyright (C) 2018 Accelerated Designs. All rights reserved")
      )
      (libsource (lib "eagle-import") (part "RB168VYM150FHTR"))
    )
    (comp (ref "JP1")
      (value "CONN_10P_CUSTOM_N2510-6002RBV02")
      (footprint "eagle-import:CONN_10P_TE_1761681-3_SE_FOR_V02")
      (fields
        (field (name "DIGI-KEY_PART_NUMBER") "1761681-3-ND")
        (field (name "MF") "TE Connectivity AMP Connectors")
        (field (name "MF_PART_NUMBER") "1761681-3")
      )
      (libsource (lib "eagle-import") (part "CONN_10P_TE_1761681-3"))
    )
    (comp (ref "LED_V1")
      (value "Blue LED")
      (footprint "eagle-import:LED_VISHAY_VLMX13XX")
      (fields
        (field (name "DIGI-KEY_PART_NUMBER") "VLMB1300-GS08CT-ND")
        (field (name "MF") "Vishay Semiconductor Opto Division")
        (field (name "MF_PART_NUMBER") "VLMB1300-GS08")
      )
      (libsource (lib "eagle-import") (part "LED_VLMB_1300"))
    )
    (comp (ref "LED_V2")
      (value "Blue LED")
      (footprint "eagle-import:LED_VISHAY_VLMX13XX")
      (fields
        (field (name "DIGI-KEY_PART_NUMBER") "VLMB1300-GS08CT-ND")
        (field (name "MF") "Vishay Semiconductor Opto Division")
        (field (name "MF_PART_NUMBER") "VLMB1300-GS08")
      )
      (libsource (lib "eagle-import") (part "LED_VLMB_1300"))
    )
    (comp (ref "LED_V3")
      (value "Blue LED")
      (footprint "eagle-import:LED_VISHAY_VLMX13XX")
      (fields
        (field (name "DIGI-KEY_PART_NUMBER") "VLMB1300-GS08CT-ND")
        (field (name "MF") "Vishay Semiconductor Opto Division")
        (field (name "MF_PART_NUMBER") "VLMB1300-GS08")
      )
      (libsource (lib "eagle-import") (part "LED_VLMB_1300"))
    )
    (comp (ref "LED_V4")
      (value "Blue LED")
      (footprint "eagle-import:LED_VISHAY_VLMX13XX")
      (fields
        (field (name "DIGI-KEY_PART_NUMBER") "VLMB1300-GS08CT-ND")
        (field (name "MF") "Vishay Semiconductor Opto Division")
        (field (name "MF_PART_NUMBER") "VLMB1300-GS08")
      )
      (libsource (lib "eagle-import") (part "LED_VLMB_1300"))
    )
    (comp (ref "LED_V5")
      (value "Blue LED")
      (footprint "eagle-import:LED_VISHAY_VLMX13XX")
      (fields
        (field (name "DIGI-KEY_PART_NUMBER") "VLMB1300-GS08CT-ND")
        (field (name "MF") "Vishay Semiconductor Opto Division")
        (field (name "MF_PART_NUMBER") "VLMB1300-GS08")
      )
      (libsource (lib "eagle-import") (part "LED_VLMB_1300"))
    )
    (comp (ref "LED_V6")
      (value "Blue LED")
      (footprint "eagle-import:LED_VISHAY_VLMX13XX")
      (fields
        (field (name "DIGI-KEY_PART_NUMBER") "VLMB1300-GS08CT-ND")
        (field (name "MF") "Vishay Semiconductor Opto Division")
        (field (name "MF_PART_NUMBER") "VLMB1300-GS08")
      )
      (libsource (lib "eagle-import") (part "LED_VLMB_1300"))
    )
    (comp (ref "LED_V7")
      (value "Blue LED")
      (footprint "eagle-import:LED_VISHAY_VLMX13XX")
      (fields
        (field (name "DIGI-KEY_PART_NUMBER") "VLMB1300-GS08CT-ND")
        (field (name "MF") "Vishay Semiconductor Opto Division")
        (field (name "MF_PART_NUMBER") "VLMB1300-GS08")
      )
      (libsource (lib "eagle-import") (part "LED_VLMB_1300"))
    )
    (comp (ref "LED_V8")
      (value "Blue LED")
      (footprint "eagle-import:LED_VISHAY_VLMX13XX")
      (fields
        (field (name "DIGI-KEY_PART_NUMBER") "VLMB1300-GS08CT-ND")
        (field (name "MF") "Vishay Semiconductor Opto Division")
        (field (name "MF_PART_NUMBER") "VLMB1300-GS08")
      )
      (libsource (lib "eagle-import") (part "LED_VLMB_1300"))
    )
    (comp (ref "R1")
      (value "10 kΩ")
      (footprint "eagle-import:BO_4816P")
      (fields
        (field (name "DIGI-KEY_PART_NUMBER") "4816P-1-103LFCT-ND ")
        (field (name "MF") "Bourns Electronics")
        (field (name "MF_PART_NUMBER") "4816P-1-103LF")
        (field (name "DIGIKEY_LINK") "https://www.digikey.com/en/products/detail/bourns-inc/4816P-1-103LF/1958036?s=N4IgTCBcDaICwA4CMA2ACgWiVgDAZgBkAxEAXQF8g")
      )
      (libsource (lib "eagle-import") (part "RES_4816P-1-103LF"))
    )
    (comp (ref "R2")
      (value "10 kΩ")
      (footprint "eagle-import:BO_4816P")
      (fields
        (field (name "DIGI-KEY_PART_NUMBER") "4816P-1-103LFCT-ND ")
        (field (name "MF") "Bourns Electronics")
        (field (name "MF_PART_NUMBER") "4816P-1-103LF")
      )
      (libsource (lib "eagle-import") (part "RES_4816P-1-103LF"))
    )
    (comp (ref "R3")
      (value "1 kΩ")
      (footprint "eagle-import:BO_4816P")
      (fields
        (field (name "DIGI-KEY_PART_NUMBER") "4816P-1-102LFCT-ND ")
        (field (name "MF") "Bourns Electronics")
        (field (name "MF_PART_NUMBER") "4816P-1-102LF")
      )
      (libsource (lib "eagle-import") (part "RES_4816P-1-102LF"))
    )
    (comp (ref "R44")
      (value "120 Ω")
      (footprint "eagle-import:RCS0603_REFLOW")
      (fields
        (field (name "DIGI-KEY_PART_NUMBER") "541-10426-1-ND")
        (field (name "MF") "Vishay")
        (field (name "MF_PART_NUMBER") "RCS0603120RFKEA")
      )
      (libsource (lib "eagle-import") (part "RCS0603120RFKEA"))
    )
    (comp (ref "R45")
      (value "120 Ω")
      (footprint "eagle-import:RCS0603_REFLOW")
      (fields
        (field (name "DIGI-KEY_PART_NUMBER") "541-10426-1-ND")
        (field (name "MF") "Vishay")
        (field (name "MF_PART_NUMBER") "RCS0603120RFKEA")
      )
      (libsource (lib "eagle-import") (part "RCS0603120RFKEA"))
    )
    (comp (ref "R46")
      (value "120 Ω")
      (footprint "eagle-import:RCS0603_REFLOW")
      (fields
        (field (name "DIGI-KEY_PART_NUMBER") "541-10426-1-ND")
        (field (name "MF") "Vishay")
        (field (name "MF_PART_NUMBER") "RCS0603120RFKEA")
      )
      (libsource (lib "eagle-import") (part "RCS0603120RFKEA"))
    )
    (comp (ref "R47")
      (value "120 Ω")
      (footprint "eagle-import:RCS0603_REFLOW")
      (fields
        (field (name "DIGI-KEY_PART_NUMBER") "541-10426-1-ND")
        (field (name "MF") "Vishay")
        (field (name "MF_PART_NUMBER") "RCS0603120RFKEA")
      )
      (libsource (lib "eagle-import") (part "RCS0603120RFKEA"))
    )
    (comp (ref "R48")
      (value "120 Ω")
      (footprint "eagle-import:RCS0603_REFLOW")
      (fields
        (field (name "DIGI-KEY_PART_NUMBER") "541-10426-1-ND")
        (field (name "MF") "Vishay")
        (field (name "MF_PART_NUMBER") "RCS0603120RFKEA")
      )
      (libsource (lib "eagle-import") (part "RCS0603120RFKEA"))
    )
    (comp (ref "R49")
      (value "120 Ω")
      (footprint "eagle-import:RCS0603_REFLOW")
      (fields
        (field (name "DIGI-KEY_PART_NUMBER") "541-10426-1-ND")
        (field (name "MF") "Vishay")
        (field (name "MF_PART_NUMBER") "RCS0603120RFKEA")
      )
      (libsource (lib "eagle-import") (part "RCS0603120RFKEA"))
    )
    (comp (ref "R50")
      (value "120 Ω")
      (footprint "eagle-import:RCS0603_REFLOW")
      (fields
        (field (name "DIGI-KEY_PART_NUMBER") "541-10426-1-ND")
        (field (name "MF") "Vishay")
        (field (name "MF_PART_NUMBER") "RCS0603120RFKEA")
      )
      (libsource (lib "eagle-import") (part "RCS0603120RFKEA"))
    )
    (comp (ref "R51")
      (value "120 Ω")
      (footprint "eagle-import:RCS0603_REFLOW")
      (fields
        (field (name "DIGI-KEY_PART_NUMBER") "541-10426-1-ND")
        (field (name "MF") "Vishay")
        (field (name "MF_PART_NUMBER") "RCS0603120RFKEA")
      )
      (libsource (lib "eagle-import") (part "RCS0603120RFKEA"))
    )
    (comp (ref "U1")
      (value "ZXMP7A17SOT223A")
      (footprint "eagle-import:SOT223")
      (fields
        (field (name "DIGI-KEY_PART_NUMBER") "ZXMP7A17GQTADICT-ND")
        (field (name "MF") "Diodes Incorporated")
        (field (name "MF_PART_NUMBER") "ZXMP7A17GQTA")
      )
      (libsource (lib "eagle-import") (part "ZXMP7A17SOT223A"))
    )
    (comp (ref "U2")
      (value "ZXMP7A17SOT223A")
      (footprint "eagle-import:SOT223")
      (fields
        (field (name "DIGI-KEY_PART_NUMBER") "ZXMP7A17GQTADICT-ND")
        (field (name "MF") "Diodes Incorporated")
        (field (name "MF_PART_NUMBER") "ZXMP7A17GQTA")
      )
      (libsource (lib "eagle-import") (part "ZXMP7A17SOT223A"))
    )
    (comp (ref "U3")
      (value "ZXMP7A17SOT223A")
      (footprint "eagle-import:SOT223")
      (fields
        (field (name "DIGI-KEY_PART_NUMBER") "ZXMP7A17GQTADICT-ND")
        (field (name "MF") "Diodes Incorporated")
        (field (name "MF_PART_NUMBER") "ZXMP7A17GQTA")
      )
      (libsource (lib "eagle-import") (part "ZXMP7A17SOT223A"))
    )
    (comp (ref "U4")
      (value "ZXMP7A17SOT223A")
      (footprint "eagle-import:SOT223")
      (fields
        (field (name "DIGI-KEY_PART_NUMBER") "ZXMP7A17GQTADICT-ND")
        (field (name "MF") "Diodes Incorporated")
        (field (name "MF_PART_NUMBER") "ZXMP7A17GQTA")
      )
      (libsource (lib "eagle-import") (part "ZXMP7A17SOT223A"))
    )
    (comp (ref "U5")
      (value "ZXMP7A17SOT223A")
      (footprint "eagle-import:SOT223")
      (fields
        (field (name "DIGI-KEY_PART_NUMBER") "ZXMP7A17GQTADICT-ND")
        (field (name "MF") "Diodes Incorporated")
        (field (name "MF_PART_NUMBER") "ZXMP7A17GQTA")
      )
      (libsource (lib "eagle-import") (part "ZXMP7A17SOT223A"))
    )
    (comp (ref "U6")
      (value "ZXMP7A17SOT223A")
      (footprint "eagle-import:SOT223")
      (fields
        (field (name "DIGI-KEY_PART_NUMBER") "ZXMP7A17GQTADICT-ND")
        (field (name "MF") "Diodes Incorporated")
        (field (name "MF_PART_NUMBER") "ZXMP7A17GQTA")
      )
      (libsource (lib "eagle-import") (part "ZXMP7A17SOT223A"))
    )
    (comp (ref "U7")
      (value "ZXMP7A17SOT223A")
      (footprint "eagle-import:SOT223")
      (fields
        (field (name "DIGI-KEY_PART_NUMBER") "ZXMP7A17GQTADICT-ND")
        (field (name "MF") "Diodes Incorporated")
        (field (name "MF_PART_NUMBER") "ZXMP7A17GQTA")
      )
      (libsource (lib "eagle-import") (part "ZXMP7A17SOT223A"))
    )
    (comp (ref "U8")
      (value "ZXMP7A17SOT223A")
      (footprint "eagle-import:SOT223")
      (fields
        (field (name "DIGI-KEY_PART_NUMBER") "ZXMP7A17GQTADICT-ND")
        (field (name "MF") "Diodes Incorporated")
        (field (name "MF_PART_NUMBER") "ZXMP7A17GQTA")
      )
      (libsource (lib "eagle-import") (part "ZXMP7A17SOT223A"))
    )
    (comp (ref "U9")
      (value "IRLML6244TR")
      (footprint "eagle-import:SOT23")
      (fields
        (field (name "DIGI-KEY_PART_NUMBER") "IRLML6244TRPBFCT-ND")
        (field (name "MF") "Infineon Technologies")
        (field (name "MF_PART_NUMBER") "IRLML6244TRPBF")
      )
      (libsource (lib "eagle-import") (part "IRLML6244TR"))
    )
    (comp (ref "U10")
      (value "IRLML6244TR")
      (footprint "eagle-import:SOT23")
      (fields
        (field (name "DIGI-KEY_PART_NUMBER") "IRLML6244TRPBFCT-ND")
        (field (name "MF") "Infineon Technologies")
        (field (name "MF_PART_NUMBER") "IRLML6244TRPBF")
      )
      (libsource (lib "eagle-import") (part "IRLML6244TR"))
    )
    (comp (ref "U11")
      (value "IRLML6244TR")
      (footprint "eagle-import:SOT23")
      (fields
        (field (name "DIGI-KEY_PART_NUMBER") "IRLML6244TRPBFCT-ND")
        (field (name "MF") "Infineon Technologies")
        (field (name "MF_PART_NUMBER") "IRLML6244TRPBF")
      )
      (libsource (lib "eagle-import") (part "IRLML6244TR"))
    )
    (comp (ref "U12")
      (value "IRLML6244TR")
      (footprint "eagle-import:SOT23")
      (fields
        (field (name "DIGI-KEY_PART_NUMBER") "IRLML6244TRPBFCT-ND")
        (field (name "MF") "Infineon Technologies")
        (field (name "MF_PART_NUMBER") "IRLML6244TRPBF")
      )
      (libsource (lib "eagle-import") (part "IRLML6244TR"))
    )
    (comp (ref "U13")
      (value "IRLML6244TR")
      (footprint "eagle-import:SOT23")
      (fields
        (field (name "DIGI-KEY_PART_NUMBER") "IRLML6244TRPBFCT-ND")
        (field (name "MF") "Infineon Technologies")
        (field (name "MF_PART_NUMBER") "IRLML6244TRPBF")
      )
      (libsource (lib "eagle-import") (part "IRLML6244TR"))
    )
    (comp (ref "U14")
      (value "IRLML6244TR")
      (footprint "eagle-import:SOT23")
      (fields
        (field (name "DIGI-KEY_PART_NUMBER") "IRLML6244TRPBFCT-ND")
        (field (name "MF") "Infineon Technologies")
        (field (name "MF_PART_NUMBER") "IRLML6244TRPBF")
      )
      (libsource (lib "eagle-import") (part "IRLML6244TR"))
    )
    (comp (ref "U15")
      (value "IRLML6244TR")
      (footprint "eagle-import:SOT23")
      (fields
        (field (name "DIGI-KEY_PART_NUMBER") "IRLML6244TRPBFCT-ND")
        (field (name "MF") "Infineon Technologies")
        (field (name "MF_PART_NUMBER") "IRLML6244TRPBF")
      )
      (libsource (lib "eagle-import") (part "IRLML6244TR"))
    )
    (comp (ref "U16")
      (value "IRLML6244TR")
      (footprint "eagle-import:SOT23")
      (fields
        (field (name "DIGI-KEY_PART_NUMBER") "IRLML6244TRPBFCT-ND")
        (field (name "MF") "Infineon Technologies")
        (field (name "MF_PART_NUMBER") "IRLML6244TRPBF")
      )
      (libsource (lib "eagle-import") (part "IRLML6244TR"))
    )
    (comp (ref "C1")
      (value "0.1 uF")
      (footprint "eagle-import:CAP_1608_TDK")
      (fields
        (field (name "DIGI-KEY_PART_NUMBER") "445-9834-1-ND ")
        (field (name "MF") "TDK Corporation")
        (field (name "MF_PART_NUMBER") "CGA3E2X7R1H104M080AD")
      )
      (libsource (lib "eagle-import") (part "CAP_CGA3E2X7R1H104M080AD"))
    )
    (comp (ref "PV1")
      (value "MOLEX_436500215PVALVES")
      (footprint "eagle-import:MOLEX_2P_PVALVES")
      (libsource (lib "eagle-import") (part "MOLEX_436500215PVALVES"))
    )
    (comp (ref "PV2")
      (value "MOLEX_436500215PVALVES")
      (footprint "eagle-import:MOLEX_2P_PVALVES")
      (libsource (lib "eagle-import") (part "MOLEX_436500215PVALVES"))
    )
    (comp (ref "PV3")
      (value "MOLEX_436500215PVALVES")
      (footprint "eagle-import:MOLEX_2P_PVALVES")
      (libsource (lib "eagle-import") (part "MOLEX_436500215PVALVES"))
    )
    (comp (ref "PV4")
      (value "MOLEX_436500215PVALVES")
      (footprint "eagle-import:MOLEX_2P_PVALVES")
      (libsource (lib "eagle-import") (part "MOLEX_436500215PVALVES"))
    )
    (comp (ref "R4")
      (value "2.2 Ω")
      (footprint "eagle-import:CRCW1206_E3_REFLOW")
      (fields
        (field (name "DIGI-KEY_PART_NUMBER") "541-2.20FFCT-ND")
        (field (name "MF") "Vishay Dale")
        (field (name "MF_PART_NUMBER") "CRCW12062R20FKEA")
      )
      (libsource (lib "eagle-import") (part "CRCW12062R20FKEA"))
    )
    (comp (ref "R5")
      (value "1 kΩ")
      (footprint "eagle-import:RES_ERJPA3F1001V")
      (fields
        (field (name "DIGI-KEY_PART_NUMBER") "P1.0KBYCT-ND")
        (field (name "MF") "Panasonic")
        (field (name "MF_PART_NUMBER") "ERJPA3F1001V")
      )
      (libsource (lib "eagle-import") (part "ERJPA3F1001V"))
    )
    (comp (ref "R6")
      (value "100 kΩ")
      (footprint "eagle-import:RESC1608X55N")
      (fields
        (field (name "DIGI-KEY_PART_NUMBER") "YAG5821CT-ND")
        (field (name "MF") "Yageo")
        (field (name "MF_PART_NUMBER") "SR0603FR-7T100KL")
      )
      (libsource (lib "eagle-import") (part "SR0603FR-7T100KL"))
    )
    (comp (ref "R7")
      (value "2.2 kΩ")
      (footprint "eagle-import:RESC1608X55N")
      (fields
        (field (name "DIGI-KEY_PART_NUMBER") "YAG5834CT-ND")
        (field (name "MF") "Yageo")
        (field (name "MF_PART_NUMBER") "SR0603FR-7T2K2L")
      )
      (libsource (lib "eagle-import") (part "SR0603FR-7T2K2L"))
    )
    (comp (ref "R8")
      (value "120 Ω")
      (footprint "eagle-import:RCS0603_REFLOW")
      (fields
        (field (name "DIGI-KEY_PART_NUMBER") "541-10426-1-ND")
        (field (name "MF") "Vishay")
        (field (name "MF_PART_NUMBER") "RCS0603120RFKEA")
      )
      (libsource (lib "eagle-import") (part "RCS0603120RFKEA"))
    )
    (comp (ref "R9")
      (value "2.2 Ω")
      (footprint "eagle-import:CRCW1206_E3_REFLOW")
      (fields
        (field (name "DIGI-KEY_PART_NUMBER") "541-2.20FFCT-ND")
        (field (name "MF") "Vishay Dale")
        (field (name "MF_PART_NUMBER") "CRCW12062R20FKEA")
      )
      (libsource (lib "eagle-import") (part "CRCW12062R20FKEA"))
    )
    (comp (ref "R10")
      (value "1 kΩ")
      (footprint "eagle-import:RES_ERJPA3F1001V")
      (fields
        (field (name "DIGI-KEY_PART_NUMBER") "P1.0KBYCT-ND")
        (field (name "MF") "Panasonic")
        (field (name "MF_PART_NUMBER") "ERJPA3F1001V")
      )
      (libsource (lib "eagle-import") (part "ERJPA3F1001V"))
    )
    (comp (ref "R11")
      (value "100 kΩ")
      (footprint "eagle-import:RESC1608X55N")
      (fields
        (field (name "DIGI-KEY_PART_NUMBER") "YAG5821CT-ND")
        (field (name "MF") "Yageo")
        (field (name "MF_PART_NUMBER") "SR0603FR-7T100KL")
      )
      (libsource (lib "eagle-import") (part "SR0603FR-7T100KL"))
    )
    (comp (ref "R12")
      (value "2.2 kΩ")
      (footprint "eagle-import:RESC1608X55N")
      (fields
        (field (name "DIGI-KEY_PART_NUMBER") "YAG5834CT-ND")
        (field (name "MF") "Yageo")
        (field (name "MF_PART_NUMBER") "SR0603FR-7T2K2L")
      )
      (libsource (lib "eagle-import") (part "SR0603FR-7T2K2L"))
    )
    (comp (ref "R13")
      (value "120 Ω")
      (footprint "eagle-import:RCS0603_REFLOW")
      (fields
        (field (name "DIGI-KEY_PART_NUMBER") "541-10426-1-ND")
        (field (name "MF") "Vishay")
        (field (name "MF_PART_NUMBER") "RCS0603120RFKEA")
      )
      (libsource (lib "eagle-import") (part "RCS0603120RFKEA"))
    )
    (comp (ref "R14")
      (value "100 kΩ")
      (footprint "eagle-import:RESC1608X55N")
      (fields
        (field (name "DIGI-KEY_PART_NUMBER") "YAG5821CT-ND")
        (field (name "MF") "Yageo")
        (field (name "MF_PART_NUMBER") "SR0603FR-7T100KL")
      )
      (libsource (lib "eagle-import") (part "SR0603FR-7T100KL"))
    )
    (comp (ref "R15")
      (value "2.2 kΩ")
      (footprint "eagle-import:RESC1608X55N")
      (fields
        (field (name "DIGI-KEY_PART_NUMBER") "YAG5834CT-ND")
        (field (name "MF") "Yageo")
        (field (name "MF_PART_NUMBER") "SR0603FR-7T2K2L")
      )
      (libsource (lib "eagle-import") (part "SR0603FR-7T2K2L"))
    )
    (comp (ref "R16")
      (value "120 Ω")
      (footprint "eagle-import:RCS0603_REFLOW")
      (fields
        (field (name "DIGI-KEY_PART_NUMBER") "541-10426-1-ND")
        (field (name "MF") "Vishay")
        (field (name "MF_PART_NUMBER") "RCS0603120RFKEA")
      )
      (libsource (lib "eagle-import") (part "RCS0603120RFKEA"))
    )
    (comp (ref "R17")
      (value "100 kΩ")
      (footprint "eagle-import:RESC1608X55N")
      (fields
        (field (name "DIGI-KEY_PART_NUMBER") "YAG5821CT-ND")
        (field (name "MF") "Yageo")
        (field (name "MF_PART_NUMBER") "SR0603FR-7T100KL")
      )
      (libsource (lib "eagle-import") (part "SR0603FR-7T100KL"))
    )
    (comp (ref "R18")
      (value "2.2 kΩ")
      (footprint "eagle-import:RESC1608X55N")
      (fields
        (field (name "DIGI-KEY_PART_NUMBER") "YAG5834CT-ND")
        (field (name "MF") "Yageo")
        (field (name "MF_PART_NUMBER") "SR0603FR-7T2K2L")
      )
      (libsource (lib "eagle-import") (part "SR0603FR-7T2K2L"))
    )
    (comp (ref "R19")
      (value "120 Ω")
      (footprint "eagle-import:RCS0603_REFLOW")
      (fields
        (field (name "DIGI-KEY_PART_NUMBER") "541-10426-1-ND")
        (field (name "MF") "Vishay")
        (field (name "MF_PART_NUMBER") "RCS0603120RFKEA")
      )
      (libsource (lib "eagle-import") (part "RCS0603120RFKEA"))
    )
    (comp (ref "R20")
      (value "2.2 Ω")
      (footprint "eagle-import:CRCW1206_E3_REFLOW")
      (fields
        (field (name "DIGI-KEY_PART_NUMBER") "541-2.20FFCT-ND")
        (field (name "MF") "Vishay Dale")
        (field (name "MF_PART_NUMBER") "CRCW12062R20FKEA")
      )
      (libsource (lib "eagle-import") (part "CRCW12062R20FKEA"))
    )
    (comp (ref "R21")
      (value "1 kΩ")
      (footprint "eagle-import:RES_ERJPA3F1001V")
      (fields
        (field (name "DIGI-KEY_PART_NUMBER") "P1.0KBYCT-ND")
        (field (name "MF") "Panasonic")
        (field (name "MF_PART_NUMBER") "ERJPA3F1001V")
      )
      (libsource (lib "eagle-import") (part "ERJPA3F1001V"))
    )
    (comp (ref "R22")
      (value "2.2 Ω")
      (footprint "eagle-import:CRCW1206_E3_REFLOW")
      (fields
        (field (name "DIGI-KEY_PART_NUMBER") "541-2.20FFCT-ND")
        (field (name "MF") "Vishay Dale")
        (field (name "MF_PART_NUMBER") "CRCW12062R20FKEA")
      )
      (libsource (lib "eagle-import") (part "CRCW12062R20FKEA"))
    )
    (comp (ref "R23")
      (value "1 kΩ")
      (footprint "eagle-import:RES_ERJPA3F1001V")
      (fields
        (field (name "DIGI-KEY_PART_NUMBER") "P1.0KBYCT-ND")
        (field (name "MF") "Panasonic")
        (field (name "MF_PART_NUMBER") "ERJPA3F1001V")
      )
      (libsource (lib "eagle-import") (part "ERJPA3F1001V"))
    )
    (comp (ref "U17")
      (value "IRLML6244TR")
      (footprint "eagle-import:SOT23")
      (fields
        (field (name "DIGI-KEY_PART_NUMBER") "IRLML6244TRPBFCT-ND")
        (field (name "MF") "Infineon Technologies")
        (field (name "MF_PART_NUMBER") "IRLML6244TRPBF")
      )
      (libsource (lib "eagle-import") (part "IRLML6244TR"))
    )
    (comp (ref "U18")
      (value "IRLML6244TR")
      (footprint "eagle-import:SOT23")
      (fields
        (field (name "DIGI-KEY_PART_NUMBER") "IRLML6244TRPBFCT-ND")
        (field (name "MF") "Infineon Technologies")
        (field (name "MF_PART_NUMBER") "IRLML6244TRPBF")
      )
      (libsource (lib "eagle-import") (part "IRLML6244TR"))
    )
    (comp (ref "U19")
      (value "IRLML6244TR")
      (footprint "eagle-import:SOT23")
      (fields
        (field (name "DIGI-KEY_PART_NUMBER") "IRLML6244TRPBFCT-ND")
        (field (name "MF") "Infineon Technologies")
        (field (name "MF_PART_NUMBER") "IRLML6244TRPBF")
      )
      (libsource (lib "eagle-import") (part "IRLML6244TR"))
    )
    (comp (ref "U20")
      (value "IRLML6244TR")
      (footprint "eagle-import:SOT23")
      (fields
        (field (name "DIGI-KEY_PART_NUMBER") "IRLML6244TRPBFCT-ND")
        (field (name "MF") "Infineon Technologies")
        (field (name "MF_PART_NUMBER") "IRLML6244TRPBF")
      )
      (libsource (lib "eagle-import") (part "IRLML6244TR"))
    )
    (comp (ref "U21")
      (value "LM324KAPWR")
      (footprint "eagle-import:SOP65P640X120-14N")
      (fields (field (name "DIGI-KEY_PART_NUMBER") "296-18449-1-ND") (field (name "MF") "Texas Instruments"))
      (libsource (lib "eagle-import") (part "LM324KAPWR"))
    )
    (comp (ref "C3")
      (value "100 uF")
      (footprint "eagle-import:CAP_J-V_10X10P5_RUB")
      (fields
        (field (name "DIGI-KEY_PART_NUMBER") "1189-2059-1-ND")
        (field (name "MF") "Rubycon")
        (field (name "MF_PART_NUMBER") "50THV100M10X10.5")
        (field (name "COPYRIGHT") "Copyright (C) 2021 Ultra Librarian. All rights reserved.")
      )
      (libsource (lib "eagle-import") (part "50THV100M10X10.5"))
    )
    (comp (ref "C4")
      (value "100 uF")
      (footprint "eagle-import:CAP_J-V_10X10P5_RUB")
      (fields
        (field (name "DIGI-KEY_PART_NUMBER") "1189-2059-1-ND")
        (field (name "MF") "Rubycon")
        (field (name "MF_PART_NUMBER") "50THV100M10X10.5")
        (field (name "COPYRIGHT") "Copyright (C) 2021 Ultra Librarian. All rights reserved.")
      )
      (libsource (lib "eagle-import") (part "50THV100M10X10.5"))
    )
    (comp (ref "C5")
      (value "100 uF")
      (footprint "eagle-import:CAP_J-V_10X10P5_RUB")
      (fields
        (field (name "DIGI-KEY_PART_NUMBER") "1189-2059-1-ND")
        (field (name "MF") "Rubycon")
        (field (name "MF_PART_NUMBER") "50THV100M10X10.5")
        (field (name "COPYRIGHT") "Copyright (C) 2021 Ultra Librarian. All rights reserved.")
      )
      (libsource (lib "eagle-import") (part "50THV100M10X10.5"))
    )
    (comp (ref "C6")
      (value "100 uF")
      (footprint "eagle-import:CAP_J-V_10X10P5_RUB")
      (fields
        (field (name "DIGI-KEY_PART_NUMBER") "1189-2059-1-ND")
        (field (name "MF") "Rubycon")
        (field (name "MF_PART_NUMBER") "50THV100M10X10.5")
        (field (name "COPYRIGHT") "Copyright (C) 2021 Ultra Librarian. All rights reserved.")
      )
      (libsource (lib "eagle-import") (part "50THV100M10X10.5"))
    )
    (comp (ref "C7")
      (value "0.1 uF")
      (footprint "eagle-import:CAP_1608_TDK")
      (fields
        (field (name "DIGI-KEY_PART_NUMBER") "445-9834-1-ND ")
        (field (name "MF") "TDK Corporation")
        (field (name "MF_PART_NUMBER") "CGA3E2X7R1H104M080AD")
      )
      (libsource (lib "eagle-import") (part "CAP_CGA3E2X7R1H104M080AD"))
    )
    (comp (ref "C8")
      (value "0.1 uF")
      (footprint "eagle-import:CAP_1608_TDK")
      (fields
        (field (name "DIGI-KEY_PART_NUMBER") "445-9834-1-ND ")
        (field (name "MF") "TDK Corporation")
        (field (name "MF_PART_NUMBER") "CGA3E2X7R1H104M080AD")
      )
      (libsource (lib "eagle-import") (part "CAP_CGA3E2X7R1H104M080AD"))
    )
    (comp (ref "C9")
      (value "10000 pF")
      (footprint "eagle-import:CAP_1608_TDK")
      (fields
        (field (name "DIGI-KEY_PART_NUMBER") "445-15955-1-ND")
        (field (name "MF") "TDK")
        (field (name "MF_PART_NUMBER") "CGA3E2X7R1H103K080AE")
        (field (name "COPYRIGHT") "Copyright (C) 2021 Ultra Librarian. All rights reserved.")
      )
      (libsource (lib "eagle-import") (part "CAP_CGA3E2X7R1H103K080AE"))
    )
    (comp (ref "C10")
      (value "10000 pF")
      (footprint "eagle-import:CAP_1608_TDK")
      (fields
        (field (name "DIGI-KEY_PART_NUMBER") "445-15955-1-ND")
        (field (name "MF") "TDK")
        (field (name "MF_PART_NUMBER") "CGA3E2X7R1H103K080AE")
        (field (name "COPYRIGHT") "Copyright (C) 2021 Ultra Librarian. All rights reserved.")
      )
      (libsource (lib "eagle-import") (part "CAP_CGA3E2X7R1H103K080AE"))
    )
    (comp (ref "HS1")
      (value "V8813W")
      (footprint "eagle-import:V8813X")
      (fields (field (name "DIGI-KEY_PART_NUMBER") "AE10771-ND") (field (name "MF") "Assmann WSW Components"))
      (libsource (lib "eagle-import") (part "V8813W"))
    )
    (comp (ref "HS2")
      (value "V8813W")
      (footprint "eagle-import:V8813X")
      (fields (field (name "DIGI-KEY_PART_NUMBER") "AE10771-ND") (field (name "MF") "Assmann WSW Components"))
      (libsource (lib "eagle-import") (part "V8813W"))
    )
    (comp (ref "J1")
      (value "PJ-037AH")
      (footprint "eagle-import:CUI_PJ-037AH")
      (fields (field (name "DIGI-KEY_PART_NUMBER") "CP-037AH-ND") (field (name "MF") "CUI Devices"))
      (libsource (lib "eagle-import") (part "PJ-037AH"))
    )
    (comp (ref "JP2")
      (value "CONN_06_HEADER")
      (footprint "eagle-import:CONN_6P_TE_1761681-1")
      (fields
        (field (name "DIGI-KEY_PART_NUMBER") "A122759-ND")
        (field (name "MF") "TE Connectivity AMP Connectors")
        (field (name "MF_PART_NUMBER") "1761681-1")
      )
      (libsource (lib "eagle-import") (part "CONN_06_HEADER"))
    )
    (comp (ref "JP3")
      (value "CONN_06_HEADER")
      (footprint "eagle-import:CONN_6P_TE_1761681-1")
      (fields
        (field (name "DIGI-KEY_PART_NUMBER") "A122759-ND")
        (field (name "MF") "TE Connectivity AMP Connectors")
        (field (name "MF_PART_NUMBER") "1761681-1")
      )
      (libsource (lib "eagle-import") (part "CONN_06_HEADER"))
    )
    (comp (ref "LED1")
      (value "Green LED")
      (footprint "eagle-import:LED_VISHAY_VLMX13XX")
      (fields
        (field (name "DIGI-KEY_PART_NUMBER") "VLMG1300-GS08CT-ND")
        (field (name "MF") "Vishay Semiconductor Opto Division")
        (field (name "MF_PART_NUMBER") "VLMG1300-GS08")
      )
      (libsource (lib "eagle-import") (part "LED_VLMG_1300"))
    )
    (comp (ref "LED2")
      (value "Green LED")
      (footprint "eagle-import:LED_VISHAY_VLMX13XX")
      (fields
        (field (name "DIGI-KEY_PART_NUMBER") "VLMG1300-GS08CT-ND")
        (field (name "MF") "Vishay Semiconductor Opto Division")
        (field (name "MF_PART_NUMBER") "VLMG1300-GS08")
      )
      (libsource (lib "eagle-import") (part "LED_VLMG_1300"))
    )
    (comp (ref "R52")
      (value "1.2 kΩ")
      (footprint "eagle-import:RCS0603_REFLOW")
      (fields
        (field (name "DIGI-KEY_PART_NUMBER") "541-10435-1-ND")
        (field (name "MF") "Vishay")
        (field (name "MF_PART_NUMBER") "RCS06031K20FKEA")
      )
      (libsource (lib "eagle-import") (part "RCS06031K20FKEA"))
    )
    (comp (ref "R53")
      (value "470 Ω")
      (footprint "eagle-import:RCS0603_REFLOW")
      (fields
        (field (name "DIGI-KEY_PART_NUMBER") "541-10469-1-ND")
        (field (name "MF") "Vishay Dale")
        (field (name "MF_PART_NUMBER") "RCS0603470RFKEA")
      )
      (libsource (lib "eagle-import") (part "RCS0603470RFKEA"))
    )
    (comp (ref "VR1")
      (value "L78S10CV")
      (footprint "eagle-import:L78S10CV")
      (fields (field (name "DIGI-KEY_PART_NUMBER") "497-6039-5-ND") (field (name "MF") "STMicroelectronics"))
      (libsource (lib "eagle-import") (part "L78S10CV"))
    )
    (comp (ref "VR2")
      (value "L78S10CV")
      (footprint "eagle-import:L78S10CV")
      (fields (field (name "DIGI-KEY_PART_NUMBER") "497-6039-5-ND") (field (name "MF") "STMicroelectronics"))
      (libsource (lib "eagle-import") (part "L78S10CV"))
    )
    (comp (ref "C2")
      (value "0.1 uF")
      (footprint "eagle-import:CAP_1608_TDK")
      (fields
        (field (name "DIGI-KEY_PART_NUMBER") "445-9834-1-ND ")
        (field (name "MF") "TDK Corporation")
        (field (name "MF_PART_NUMBER") "CGA3E2X7R1H104M080AD")
      )
      (libsource (lib "eagle-import") (part "CAP_CGA3E2X7R1H104M080AD"))
    )
    (comp (ref "PV5")
      (value "MOLEX_436500215PVALVES")
      (footprint "eagle-import:MOLEX_2P_PVALVES")
      (libsource (lib "eagle-import") (part "MOLEX_436500215PVALVES"))
    )
    (comp (ref "PV6")
      (value "MOLEX_436500215PVALVES")
      (footprint "eagle-import:MOLEX_2P_PVALVES")
      (libsource (lib "eagle-import") (part "MOLEX_436500215PVALVES"))
    )
    (comp (ref "PV7")
      (value "MOLEX_436500215PVALVES")
      (footprint "eagle-import:MOLEX_2P_PVALVES")
      (libsource (lib "eagle-import") (part "MOLEX_436500215PVALVES"))
    )
    (comp (ref "PV8")
      (value "MOLEX_436500215PVALVES")
      (footprint "eagle-import:MOLEX_2P_PVALVES")
      (libsource (lib "eagle-import") (part "MOLEX_436500215PVALVES"))
    )
    (comp (ref "R24")
      (value "2.2 Ω")
      (footprint "eagle-import:CRCW1206_E3_REFLOW")
      (fields
        (field (name "DIGI-KEY_PART_NUMBER") "541-2.20FFCT-ND")
        (field (name "MF") "Vishay Dale")
        (field (name "MF_PART_NUMBER") "CRCW12062R20FKEA")
      )
      (libsource (lib "eagle-import") (part "CRCW12062R20FKEA"))
    )
    (comp (ref "R25")
      (value "1 kΩ")
      (footprint "eagle-import:RES_ERJPA3F1001V")
      (fields
        (field (name "DIGI-KEY_PART_NUMBER") "P1.0KBYCT-ND")
        (field (name "MF") "Panasonic")
        (field (name "MF_PART_NUMBER") "ERJPA3F1001V")
      )
      (libsource (lib "eagle-import") (part "ERJPA3F1001V"))
    )
    (comp (ref "R26")
      (value "100 kΩ")
      (footprint "eagle-import:RESC1608X55N")
      (fields
        (field (name "DIGI-KEY_PART_NUMBER") "YAG5821CT-ND")
        (field (name "MF") "Yageo")
        (field (name "MF_PART_NUMBER") "SR0603FR-7T100KL")
      )
      (libsource (lib "eagle-import") (part "SR0603FR-7T100KL"))
    )
    (comp (ref "R27")
      (value "2.2 kΩ")
      (footprint "eagle-import:RESC1608X55N")
      (fields
        (field (name "DIGI-KEY_PART_NUMBER") "YAG5834CT-ND")
        (field (name "MF") "Yageo")
        (field (name "MF_PART_NUMBER") "SR0603FR-7T2K2L")
      )
      (libsource (lib "eagle-import") (part "SR0603FR-7T2K2L"))
    )
    (comp (ref "R28")
      (value "120 Ω")
      (footprint "eagle-import:RCS0603_REFLOW")
      (fields
        (field (name "DIGI-KEY_PART_NUMBER") "541-10426-1-ND")
        (field (name "MF") "Vishay")
        (field (name "MF_PART_NUMBER") "RCS0603120RFKEA")
      )
      (libsource (lib "eagle-import") (part "RCS0603120RFKEA"))
    )
    (comp (ref "R29")
      (value "2.2 Ω")
      (footprint "eagle-import:CRCW1206_E3_REFLOW")
      (fields
        (field (name "DIGI-KEY_PART_NUMBER") "541-2.20FFCT-ND")
        (field (name "MF") "Vishay Dale")
        (field (name "MF_PART_NUMBER") "CRCW12062R20FKEA")
      )
      (libsource (lib "eagle-import") (part "CRCW12062R20FKEA"))
    )
    (comp (ref "R30")
      (value "1 kΩ")
      (footprint "eagle-import:RES_ERJPA3F1001V")
      (fields
        (field (name "DIGI-KEY_PART_NUMBER") "P1.0KBYCT-ND")
        (field (name "MF") "Panasonic")
        (field (name "MF_PART_NUMBER") "ERJPA3F1001V")
      )
      (libsource (lib "eagle-import") (part "ERJPA3F1001V"))
    )
    (comp (ref "R31")
      (value "100 kΩ")
      (footprint "eagle-import:RESC1608X55N")
      (fields
        (field (name "DIGI-KEY_PART_NUMBER") "YAG5821CT-ND")
        (field (name "MF") "Yageo")
        (field (name "MF_PART_NUMBER") "SR0603FR-7T100KL")
      )
      (libsource (lib "eagle-import") (part "SR0603FR-7T100KL"))
    )
    (comp (ref "R32")
      (value "2.2 kΩ")
      (footprint "eagle-import:RESC1608X55N")
      (fields
        (field (name "DIGI-KEY_PART_NUMBER") "YAG5834CT-ND")
        (field (name "MF") "Yageo")
        (field (name "MF_PART_NUMBER") "SR0603FR-7T2K2L")
      )
      (libsource (lib "eagle-import") (part "SR0603FR-7T2K2L"))
    )
    (comp (ref "R33")
      (value "120 Ω")
      (footprint "eagle-import:RCS0603_REFLOW")
      (fields
        (field (name "DIGI-KEY_PART_NUMBER") "541-10426-1-ND")
        (field (name "MF") "Vishay")
        (field (name "MF_PART_NUMBER") "RCS0603120RFKEA")
      )
      (libsource (lib "eagle-import") (part "RCS0603120RFKEA"))
    )
    (comp (ref "R34")
      (value "100 kΩ")
      (footprint "eagle-import:RESC1608X55N")
      (fields
        (field (name "DIGI-KEY_PART_NUMBER") "YAG5821CT-ND")
        (field (name "MF") "Yageo")
        (field (name "MF_PART_NUMBER") "SR0603FR-7T100KL")
      )
      (libsource (lib "eagle-import") (part "SR0603FR-7T100KL"))
    )
    (comp (ref "R35")
      (value "2.2 kΩ")
      (footprint "eagle-import:RESC1608X55N")
      (fields
        (field (name "DIGI-KEY_PART_NUMBER") "YAG5834CT-ND")
        (field (name "MF") "Yageo")
        (field (name "MF_PART_NUMBER") "SR0603FR-7T2K2L")
      )
      (libsource (lib "eagle-import") (part "SR0603FR-7T2K2L"))
    )
    (comp (ref "R36")
      (value "120 Ω")
      (footprint "eagle-import:RCS0603_REFLOW")
      (fields
        (field (name "DIGI-KEY_PART_NUMBER") "541-10426-1-ND")
        (field (name "MF") "Vishay")
        (field (name "MF_PART_NUMBER") "RCS0603120RFKEA")
      )
      (libsource (lib "eagle-import") (part "RCS0603120RFKEA"))
    )
    (comp (ref "R37")
      (value "100 kΩ")
      (footprint "eagle-import:RESC1608X55N")
      (fields
        (field (name "DIGI-KEY_PART_NUMBER") "YAG5821CT-ND")
        (field (name "MF") "Yageo")
        (field (name "MF_PART_NUMBER") "SR0603FR-7T100KL")
      )
      (libsource (lib "eagle-import") (part "SR0603FR-7T100KL"))
    )
    (comp (ref "R38")
      (value "2.2 kΩ")
      (footprint "eagle-import:RESC1608X55N")
      (fields
        (field (name "DIGI-KEY_PART_NUMBER") "YAG5834CT-ND")
        (field (name "MF") "Yageo")
        (field (name "MF_PART_NUMBER") "SR0603FR-7T2K2L")
      )
      (libsource (lib "eagle-import") (part "SR0603FR-7T2K2L"))
    )
    (comp (ref "R39")
      (value "120 Ω")
      (footprint "eagle-import:RCS0603_REFLOW")
      (fields
        (field (name "DIGI-KEY_PART_NUMBER") "541-10426-1-ND")
        (field (name "MF") "Vishay")
        (field (name "MF_PART_NUMBER") "RCS0603120RFKEA")
      )
      (libsource (lib "eagle-import") (part "RCS0603120RFKEA"))
    )
    (comp (ref "R40")
      (value "2.2 Ω")
      (footprint "eagle-import:CRCW1206_E3_REFLOW")
      (fields
        (field (name "DIGI-KEY_PART_NUMBER") "541-2.20FFCT-ND")
        (field (name "MF") "Vishay Dale")
        (field (name "MF_PART_NUMBER") "CRCW12062R20FKEA")
      )
      (libsource (lib "eagle-import") (part "CRCW12062R20FKEA"))
    )
    (comp (ref "R41")
      (value "1 kΩ")
      (footprint "eagle-import:RES_ERJPA3F1001V")
      (fields
        (field (name "DIGI-KEY_PART_NUMBER") "P1.0KBYCT-ND")
        (field (name "MF") "Panasonic")
        (field (name "MF_PART_NUMBER") "ERJPA3F1001V")
      )
      (libsource (lib "eagle-import") (part "ERJPA3F1001V"))
    )
    (comp (ref "R42")
      (value "2.2 Ω")
      (footprint "eagle-import:CRCW1206_E3_REFLOW")
      (fields
        (field (name "DIGI-KEY_PART_NUMBER") "541-2.20FFCT-ND")
        (field (name "MF") "Vishay Dale")
        (field (name "MF_PART_NUMBER") "CRCW12062R20FKEA")
      )
      (libsource (lib "eagle-import") (part "CRCW12062R20FKEA"))
    )
    (comp (ref "R43")
      (value "1 kΩ")
      (footprint "eagle-import:RES_ERJPA3F1001V")
      (fields
        (field (name "DIGI-KEY_PART_NUMBER") "P1.0KBYCT-ND")
        (field (name "MF") "Panasonic")
        (field (name "MF_PART_NUMBER") "ERJPA3F1001V")
      )
      (libsource (lib "eagle-import") (part "ERJPA3F1001V"))
    )
    (comp (ref "U22")
      (value "IRLML6244TR")
      (footprint "eagle-import:SOT23")
      (fields
        (field (name "DIGI-KEY_PART_NUMBER") "IRLML6244TRPBFCT-ND")
        (field (name "MF") "Infineon Technologies")
        (field (name "MF_PART_NUMBER") "IRLML6244TRPBF")
      )
      (libsource (lib "eagle-import") (part "IRLML6244TR"))
    )
    (comp (ref "U23")
      (value "IRLML6244TR")
      (footprint "eagle-import:SOT23")
      (fields
        (field (name "DIGI-KEY_PART_NUMBER") "IRLML6244TRPBFCT-ND")
        (field (name "MF") "Infineon Technologies")
        (field (name "MF_PART_NUMBER") "IRLML6244TRPBF")
      )
      (libsource (lib "eagle-import") (part "IRLML6244TR"))
    )
    (comp (ref "U24")
      (value "IRLML6244TR")
      (footprint "eagle-import:SOT23")
      (fields
        (field (name "DIGI-KEY_PART_NUMBER") "IRLML6244TRPBFCT-ND")
        (field (name "MF") "Infineon Technologies")
        (field (name "MF_PART_NUMBER") "IRLML6244TRPBF")
      )
      (libsource (lib "eagle-import") (part "IRLML6244TR"))
    )
    (comp (ref "U25")
      (value "IRLML6244TR")
      (footprint "eagle-import:SOT23")
      (fields
        (field (name "DIGI-KEY_PART_NUMBER") "IRLML6244TRPBFCT-ND")
        (field (name "MF") "Infineon Technologies")
        (field (name "MF_PART_NUMBER") "IRLML6244TRPBF")
      )
      (libsource (lib "eagle-import") (part "IRLML6244TR"))
    )
    (comp (ref "U26")
      (value "LM324KAPWR")
      (footprint "eagle-import:SOP65P640X120-14N")
      (fields (field (name "DIGI-KEY_PART_NUMBER") "296-18449-1-ND") (field (name "MF") "Texas Instruments"))
      (libsource (lib "eagle-import") (part "LM324KAPWR"))
    )
    (comp (ref "FL1")
      (value "CONN_03_FL")
      (footprint "eagle-import:1X03_FL")
      (fields
        (field (name "DIGI-KEY_PART_NUMBER") "S7036-ND")
        (field (name "MF") "Sullins Connector Solutions")
        (field (name "MF_PART_NUMBER") "PPPC031LFBN-RC")
      )
      (libsource (lib "eagle-import") (part "CONN_03_FL"))
    )
    (comp (ref "FL2")
      (value "CONN_03_FL")
      (footprint "eagle-import:1X03_FL")
      (fields
        (field (name "DIGI-KEY_PART_NUMBER") "S7036-ND")
        (field (name "MF") "Sullins Connector Solutions")
        (field (name "MF_PART_NUMBER") "PPPC031LFBN-RC")
      )
      (libsource (lib "eagle-import") (part "CONN_03_FL"))
    )
    (comp (ref "FL3")
      (value "CONN_03_FL")
      (footprint "eagle-import:1X03_FL")
      (fields
        (field (name "DIGI-KEY_PART_NUMBER") "S7036-ND")
        (field (name "MF") "Sullins Connector Solutions")
        (field (name "MF_PART_NUMBER") "PPPC031LFBN-RC")
      )
      (libsource (lib "eagle-import") (part "CONN_03_FL"))
    )
    (comp (ref "FL4")
      (value "CONN_03_FL")
      (footprint "eagle-import:1X03_FL")
      (fields
        (field (name "DIGI-KEY_PART_NUMBER") "S7036-ND")
        (field (name "MF") "Sullins Connector Solutions")
        (field (name "MF_PART_NUMBER") "PPPC031LFBN-RC")
      )
      (libsource (lib "eagle-import") (part "CONN_03_FL"))
    )
    (comp (ref "FL5")
      (value "CONN_03_FL")
      (footprint "eagle-import:1X03_FL")
      (fields
        (field (name "DIGI-KEY_PART_NUMBER") "S7036-ND")
        (field (name "MF") "Sullins Connector Solutions")
        (field (name "MF_PART_NUMBER") "PPPC031LFBN-RC")
      )
      (libsource (lib "eagle-import") (part "CONN_03_FL"))
    )
    (comp (ref "FL6")
      (value "CONN_03_FL")
      (footprint "eagle-import:1X03_FL")
      (fields
        (field (name "DIGI-KEY_PART_NUMBER") "S7036-ND")
        (field (name "MF") "Sullins Connector Solutions")
        (field (name "MF_PART_NUMBER") "PPPC031LFBN-RC")
      )
      (libsource (lib "eagle-import") (part "CONN_03_FL"))
    )
    (comp (ref "FL7")
      (value "CONN_03_FL")
      (footprint "eagle-import:1X03_FL")
      (fields
        (field (name "DIGI-KEY_PART_NUMBER") "S7036-ND")
        (field (name "MF") "Sullins Connector Solutions")
        (field (name "MF_PART_NUMBER") "PPPC031LFBN-RC")
      )
      (libsource (lib "eagle-import") (part "CONN_03_FL"))
    )
    (comp (ref "FL8")
      (value "CONN_03_FL")
      (footprint "eagle-import:1X03_FL")
      (fields
        (field (name "DIGI-KEY_PART_NUMBER") "S7036-ND")
        (field (name "MF") "Sullins Connector Solutions")
        (field (name "MF_PART_NUMBER") "PPPC031LFBN-RC")
      )
      (libsource (lib "eagle-import") (part "CONN_03_FL"))
    )
    (comp (ref "J2")
      (value "MOLEX_436500415")
      (footprint "eagle-import:MOLEX_4P_FOOTPRINT")
      (fields
        (field (name "DIGI-KEY_PART_NUMBER") "WM1919-ND")
        (field (name "MF") "Molex")
        (field (name "MF_PART_NUMBER") "0436500415")
      )
      (libsource (lib "eagle-import") (part "MOLEX_436500415"))
    )
    (comp (ref "S1")
      (value "1-1825059-7")
      (footprint "eagle-import:SW_1-1825059-7")
      (fields (field (name "DIGI-KEY_PART_NUMBER") "1-1825059-7-ND") (field (name "MF") "TE Connectivity"))
      (libsource (lib "eagle-import") (part "1-1825059-7"))
    )
    (comp (ref "X1")
      (value "ARDUINO_MEGA2560_HEADERPINSXX")
      (footprint "eagle-import:ARDUINO_MEGA2560_ST_FLIPPED_CUTS")
      (libsource (lib "eagle-import") (part "ARDUINO_MEGA2560"))
    )
  )
  (nets
    (net (code "1") (name "+10V") (class "Default")
      (node (ref "C3") (pin "+") (pinfunction "+_+") (pintype "passive"))
      (node (ref "C4") (pin "+") (pinfunction "+_+") (pintype "passive"))
      (node (ref "C7") (pin "1") (pinfunction "1_1") (pintype "passive"))
      (node (ref "C9") (pin "1") (pinfunction "1_1") (pintype "passive"))
      (node (ref "FL1") (pin "2") (pinfunction "2_2") (pintype "passive"))
      (node (ref "FL2") (pin "2") (pinfunction "2_2") (pintype "passive"))
      (node (ref "FL3") (pin "2") (pinfunction "2_2") (pintype "passive"))
      (node (ref "FL4") (pin "2") (pinfunction "2_2") (pintype "passive"))
      (node (ref "FL5") (pin "2") (pinfunction "2_2") (pintype "passive"))
      (node (ref "FL6") (pin "2") (pinfunction "2_2") (pintype "passive"))
      (node (ref "FL7") (pin "2") (pinfunction "2_2") (pintype "passive"))
      (node (ref "FL8") (pin "2") (pinfunction "2_2") (pintype "passive"))
      (node (ref "FL9") (pin "2") (pinfunction "2_2") (pintype "passive"))
      (node (ref "R53") (pin "2") (pinfunction "2_2") (pintype "passive"))
      (node (ref "U17") (pin "3") (pinfunction "D_3") (pintype "passive"))
      (node (ref "U18") (pin "3") (pinfunction "D_3") (pintype "passive"))
      (node (ref "U19") (pin "3") (pinfunction "D_3") (pintype "passive"))
      (node (ref "U20") (pin "3") (pinfunction "D_3") (pintype "passive"))
      (node (ref "U22") (pin "3") (pinfunction "D_3") (pintype "passive"))
      (node (ref "U23") (pin "3") (pinfunction "D_3") (pintype "passive"))
      (node (ref "U24") (pin "3") (pinfunction "D_3") (pintype "passive"))
      (node (ref "U25") (pin "3") (pinfunction "D_3") (pintype "passive"))
      (node (ref "U31") (pin "3") (pinfunction "D_3") (pintype "passive"))
      (node (ref "VR1") (pin "3") (pinfunction "OUT_3") (pintype "output"))
      (node (ref "VR2") (pin "3") (pinfunction "OUT_3") (pintype "output"))
      (node (ref "X1") (pin "VIN") (pinfunction "VIN_VIN") (pintype "bidirectional"))
    )
    (net (code "2") (name "+24V") (class "Default")
      (node (ref "C1") (pin "1") (pinfunction "1_1") (pintype "passive"))
      (node (ref "C10") (pin "1") (pinfunction "1_1") (pintype "passive"))
      (node (ref "C2") (pin "1") (pinfunction "1_1") (pintype "passive"))
      (node (ref "C5") (pin "+") (pinfunction "+_+") (pintype "passive"))
      (node (ref "C6") (pin "+") (pinfunction "+_+") (pintype "passive"))
      (node (ref "C8") (pin "1") (pinfunction "1_1") (pintype "passive"))
      (node (ref "IC1") (pin "5") (pinfunction "V+_5") (pintype "bidirectional"))
      (node (ref "J1") (pin "1") (pinfunction "1_1") (pintype "passive"))
      (node (ref "JP2") (pin "4") (pinfunction "4_4") (pintype "passive"))
      (node (ref "JP3") (pin "4") (pinfunction "4_4") (pintype "passive"))
      (node (ref "JP4") (pin "2") (pinfunction "2_2") (pintype "passive"))
      (node (ref "R1") (pin "1") (pinfunction "1_1") (pintype "passive"))
      (node (ref "R1") (pin "2") (pinfunction "2_2") (pintype "passive"))
      (node (ref "R1") (pin "3") (pinfunction "3_3") (pintype "passive"))
      (node (ref "R1") (pin "4") (pinfunction "4_4") (pintype "passive"))
      (node (ref "R1") (pin "5") (pinfunction "5_5") (pintype "passive"))
      (node (ref "R1") (pin "6") (pinfunction "6_6") (pintype "passive"))
      (node (ref "R1") (pin "7") (pinfunction "7_7") (pintype "passive"))
      (node (ref "R1") (pin "8") (pinfunction "8_8") (pintype "passive"))
      (node (ref "R52") (pin "2") (pinfunction "2_2") (pintype "passive"))
      (node (ref "R56") (pin "2") (pinfunction "2_2") (pintype "passive"))
      (node (ref "R59") (pin "2") (pinfunction "2_2") (pintype "passive"))
      (node (ref "U1") (pin "3") (pinfunction "S_3") (pintype "passive"))
      (node (ref "U2") (pin "3") (pinfunction "S_3") (pintype "passive"))
      (node (ref "U21") (pin "4") (pinfunction "VCC_4") (pintype "passive"))
      (node (ref "U26") (pin "4") (pinfunction "VCC_4") (pintype "passive"))
      (node (ref "U28") (pin "3") (pinfunction "S_3") (pintype "passive"))
      (node (ref "U3") (pin "3") (pinfunction "S_3") (pintype "passive"))
      (node (ref "U30") (pin "3") (pinfunction "S_3") (pintype "passive"))
      (node (ref "U4") (pin "3") (pinfunction "S_3") (pintype "passive"))
      (node (ref "U5") (pin "3") (pinfunction "S_3") (pintype "passive"))
      (node (ref "U6") (pin "3") (pinfunction "S_3") (pintype "passive"))
      (node (ref "U7") (pin "3") (pinfunction "S_3") (pintype "passive"))
      (node (ref "U8") (pin "3") (pinfunction "S_3") (pintype "passive"))
      (node (ref "VR1") (pin "1") (pinfunction "IN_1") (pintype "input"))
      (node (ref "VR2") (pin "1") (pinfunction "IN_1") (pintype "input"))
    )
    (net (code "3") (name "GNDA") (class "Default")
      (node (ref "C1") (pin "2") (pinfunction "2_2") (pintype "passive"))
      (node (ref "C10") (pin "2") (pinfunction "2_2") (pintype "passive"))
      (node (ref "C2") (pin "2") (pinfunction "2_2") (pintype "passive"))
      (node (ref "C3") (pin "-") (pinfunction "-_-") (pintype "passive"))
      (node (ref "C4") (pin "-") (pinfunction "-_-") (pintype "passive"))
      (node (ref "C5") (pin "-") (pinfunction "-_-") (pintype "passive"))
      (node (ref "C6") (pin "-") (pinfunction "-_-") (pintype "passive"))
      (node (ref "C7") (pin "2") (pinfunction "2_2") (pintype "passive"))
      (node (ref "C8") (pin "2") (pinfunction "2_2") (pintype "passive"))
      (node (ref "C9") (pin "2") (pinfunction "2_2") (pintype "passive"))
      (node (ref "D1") (pin "2") (pinfunction "A_2") (pintype "passive"))
      (node (ref "D10") (pin "2") (pinfunction "A_2") (pintype "passive"))
      (node (ref "D2") (pin "2") (pinfunction "A_2") (pintype "passive"))
      (node (ref "D3") (pin "2") (pinfunction "A_2") (pintype "passive"))
      (node (ref "D4") (pin "2") (pinfunction "A_2") (pintype "passive"))
      (node (ref "D5") (pin "2") (pinfunction "A_2") (pintype "passive"))
      (node (ref "D6") (pin "2") (pinfunction "A_2") (pintype "passive"))
      (node (ref "D7") (pin "2") (pinfunction "A_2") (pintype "passive"))
      (node (ref "D8") (pin "2") (pinfunction "A_2") (pintype "passive"))
      (node (ref "D9") (pin "2") (pinfunction "A_2") (pintype "passive"))
      (node (ref "FL1") (pin "3") (pinfunction "3_3") (pintype "passive"))
      (node (ref "FL2") (pin "3") (pinfunction "3_3") (pintype "passive"))
      (node (ref "FL3") (pin "3") (pinfunction "3_3") (pintype "passive"))
      (node (ref "FL4") (pin "3") (pinfunction "3_3") (pintype "passive"))
      (node (ref "FL5") (pin "3") (pinfunction "3_3") (pintype "passive"))
      (node (ref "FL6") (pin "3") (pinfunction "3_3") (pintype "passive"))
      (node (ref "FL7") (pin "3") (pinfunction "3_3") (pintype "passive"))
      (node (ref "FL8") (pin "3") (pinfunction "3_3") (pintype "passive"))
      (node (ref "FL9") (pin "3") (pinfunction "3_3") (pintype "passive"))
      (node (ref "IC1") (pin "2") (pinfunction "V-_2") (pintype "bidirectional"))
      (node (ref "J1") (pin "2") (pinfunction "2_2") (pintype "passive"))
      (node (ref "J2") (pin "1") (pinfunction "1_1") (pintype "passive"))
      (node (ref "J2") (pin "3") (pinfunction "3_3") (pintype "passive"))
      (node (ref "J3") (pin "2") (pinfunction "2_2") (pintype "passive"))
      (node (ref "J4") (pin "2") (pinfunction "2_2") (pintype "passive"))
      (node (ref "JP1") (pin "GND") (pinfunction "GND_GND") (pintype "passive"))
      (node (ref "JP1") (pin "GND.") (pinfunction "GND1_GND.") (pintype "passive"))
      (node (ref "JP2") (pin "2") (pinfunction "2_2") (pintype "passive"))
      (node (ref "JP2") (pin "3") (pinfunction "3_3") (pintype "passive"))
      (node (ref "JP2") (pin "6") (pinfunction "6_6") (pintype "passive"))
      (node (ref "JP3") (pin "2") (pinfunction "2_2") (pintype "passive"))
      (node (ref "JP3") (pin "3") (pinfunction "3_3") (pintype "passive"))
      (node (ref "JP3") (pin "6") (pinfunction "6_6") (pintype "passive"))
      (node (ref "JP4") (pin "1") (pinfunction "1_1") (pintype "passive"))
      (node (ref "LED1") (pin "C") (pinfunction "C_C") (pintype "passive"))
      (node (ref "LED2") (pin "C") (pinfunction "C_C") (pintype "passive"))
      (node (ref "LED_V1") (pin "C") (pinfunction "C_C") (pintype "passive"))
      (node (ref "LED_V10") (pin "C") (pinfunction "C_C") (pintype "passive"))
      (node (ref "LED_V2") (pin "C") (pinfunction "C_C") (pintype "passive"))
      (node (ref "LED_V3") (pin "C") (pinfunction "C_C") (pintype "passive"))
      (node (ref "LED_V4") (pin "C") (pinfunction "C_C") (pintype "passive"))
      (node (ref "LED_V5") (pin "C") (pinfunction "C_C") (pintype "passive"))
      (node (ref "LED_V6") (pin "C") (pinfunction "C_C") (pintype "passive"))
      (node (ref "LED_V7") (pin "C") (pinfunction "C_C") (pintype "passive"))
      (node (ref "LED_V8") (pin "C") (pinfunction "C_C") (pintype "passive"))
      (node (ref "LED_V9") (pin "C") (pinfunction "C_C") (pintype "passive"))
      (node (ref "R13") (pin "1") (pinfunction "1_1") (pintype "passive"))
      (node (ref "R16") (pin "1") (pinfunction "1_1") (pintype "passive"))
      (node (ref "R19") (pin "1") (pinfunction "1_1") (pintype "passive"))
      (node (ref "R2") (pin "1") (pinfunction "1_1") (pintype "passive"))
      (node (ref "R2") (pin "2") (pinfunction "2_2") (pintype "passive"))
      (node (ref "R2") (pin "3") (pinfunction "3_3") (pintype "passive"))
      (node (ref "R2") (pin "4") (pinfunction "4_4") (pintype "passive"))
      (node (ref "R2") (pin "5") (pinfunction "5_5") (pintype "passive"))
      (node (ref "R2") (pin "6") (pinfunction "6_6") (pintype "passive"))
      (node (ref "R2") (pin "7") (pinfunction "7_7") (pintype "passive"))
      (node (ref "R2") (pin "8") (pinfunction "8_8") (pintype "passive"))
      (node (ref "R20") (pin "1") (pinfunction "1_1") (pintype "passive"))
      (node (ref "R22") (pin "1") (pinfunction "1_1") (pintype "passive"))
      (node (ref "R24") (pin "1") (pinfunction "1_1") (pintype "passive"))
      (node (ref "R28") (pin "1") (pinfunction "1_1") (pintype "passive"))
      (node (ref "R29") (pin "1") (pinfunction "1_1") (pintype "passive"))
      (node (ref "R33") (pin "1") (pinfunction "1_1") (pintype "passive"))
      (node (ref "R36") (pin "1") (pinfunction "1_1") (pintype "passive"))
      (node (ref "R39") (pin "1") (pinfunction "1_1") (pintype "passive"))
      (node (ref "R4") (pin "1") (pinfunction "1_1") (pintype "passive"))
      (node (ref "R40") (pin "1") (pinfunction "1_1") (pintype "passive"))
      (node (ref "R42") (pin "1") (pinfunction "1_1") (pintype "passive"))
      (node (ref "R55") (pin "1") (pinfunction "1_1") (pintype "passive"))
      (node (ref "R58") (pin "1") (pinfunction "1_1") (pintype "passive"))
      (node (ref "R64") (pin "1") (pinfunction "1_1") (pintype "passive"))
      (node (ref "R65") (pin "1") (pinfunction "1_1") (pintype "passive"))
      (node (ref "R8") (pin "1") (pinfunction "1_1") (pintype "passive"))
      (node (ref "R9") (pin "1") (pinfunction "1_1") (pintype "passive"))
      (node (ref "S1") (pin "1") (pinfunction "1_1") (pintype "passive"))
      (node (ref "S1") (pin "2") (pinfunction "2_2") (pintype "passive"))
      (node (ref "S1") (pin "3") (pinfunction "3_3") (pintype "passive"))
      (node (ref "S1") (pin "4") (pinfunction "4_4") (pintype "passive"))
      (node (ref "U10") (pin "2") (pinfunction "S_2") (pintype "passive"))
      (node (ref "U11") (pin "2") (pinfunction "S_2") (pintype "passive"))
      (node (ref "U12") (pin "2") (pinfunction "S_2") (pintype "passive"))
      (node (ref "U13") (pin "2") (pinfunction "S_2") (pintype "passive"))
      (node (ref "U14") (pin "2") (pinfunction "S_2") (pintype "passive"))
      (node (ref "U15") (pin "2") (pinfunction "S_2") (pintype "passive"))
      (node (ref "U16") (pin "2") (pinfunction "S_2") (pintype "passive"))
      (node (ref "U21") (pin "11") (pinfunction "GND_11") (pintype "passive"))
      (node (ref "U26") (pin "11") (pinfunction "GND_11") (pintype "passive"))
      (node (ref "U27") (pin "2") (pinfunction "S_2") (pintype "passive"))
      (node (ref "U29") (pin "2") (pinfunction "S_2") (pintype "passive"))
      (node (ref "U9") (pin "2") (pinfunction "S_2") (pintype "passive"))
      (node (ref "VR1") (pin "2") (pinfunction "GND_2") (pintype "power_in"))
      (node (ref "VR2") (pin "2") (pinfunction "GND_2") (pintype "power_in"))
      (node (ref "X1") (pin "GND") (pinfunction "GND_GND") (pintype "bidirectional"))
      (node (ref "X1") (pin "GND.") (pinfunction "GND_GND.") (pintype "bidirectional"))
      (node (ref "X1") (pin "GND..") (pinfunction "GND_GND..") (pintype "bidirectional"))
    )
    (net (code "4") (name "MC_V1") (class "Default")
      (node (ref "D1") (pin "1") (pinfunction "C_1") (pintype "passive"))
      (node (ref "JP1") (pin "V1") (pinfunction "V1_V1") (pintype "passive"))
      (node (ref "U1") (pin "2") (pinfunction "D_2") (pintype "passive"))
      (node (ref "U1") (pin "4") (pinfunction "D_4") (pintype "passive"))
    )
    (net (code "5") (name "MC_V2") (class "Default")
      (node (ref "D2") (pin "1") (pinfunction "C_1") (pintype "passive"))
      (node (ref "JP1") (pin "V2") (pinfunction "V2_V2") (pintype "passive"))
      (node (ref "U2") (pin "2") (pinfunction "D_2") (pintype "passive"))
      (node (ref "U2") (pin "4") (pinfunction "D_4") (pintype "passive"))
    )
    (net (code "6") (name "MC_V3") (class "Default")
      (node (ref "D3") (pin "1") (pinfunction "C_1") (pintype "passive"))
      (node (ref "JP1") (pin "V3") (pinfunction "V3_V3") (pintype "passive"))
      (node (ref "U3") (pin "2") (pinfunction "D_2") (pintype "passive"))
      (node (ref "U3") (pin "4") (pinfunction "D_4") (pintype "passive"))
    )
    (net (code "7") (name "MC_V4") (class "Default")
      (node (ref "D4") (pin "1") (pinfunction "C_1") (pintype "passive"))
      (node (ref "JP1") (pin "V4") (pinfunction "V4_V4") (pintype "passive"))
      (node (ref "U4") (pin "2") (pinfunction "D_2") (pintype "passive"))
      (node (ref "U4") (pin "4") (pinfunction "D_4") (pintype "passive"))
    )
    (net (code "8") (name "MC_V5") (class "Default")
      (node (ref "D5") (pin "1") (pinfunction "C_1") (pintype "passive"))
      (node (ref "JP1") (pin "V5") (pinfunction "V5_V5") (pintype "passive"))
      (node (ref "U5") (pin "2") (pinfunction "D_2") (pintype "passive"))
      (node (ref "U5") (pin "4") (pinfunction "D_4") (pintype "passive"))
    )
    (net (code "9") (name "MC_V6") (class "Default")
      (node (ref "D6") (pin "1") (pinfunction "C_1") (pintype "passive"))
      (node (ref "JP1") (pin "V6") (pinfunction "V6_V6") (pintype "passive"))
      (node (ref "U6") (pin "2") (pinfunction "D_2") (pintype "passive"))
      (node (ref "U6") (pin "4") (pinfunction "D_4") (pintype "passive"))
    )
    (net (code "10") (name "MC_V7") (class "Default")
      (node (ref "D7") (pin "1") (pinfunction "C_1") (pintype "passive"))
      (node (ref "JP1") (pin "V7") (pinfunction "V7_V7") (pintype "passive"))
      (node (ref "U7") (pin "2") (pinfunction "D_2") (pintype "passive"))
      (node (ref "U7") (pin "4") (pinfunction "D_4") (pintype "passive"))
    )
    (net (code "11") (name "MC_V8") (class "Default")
      (node (ref "D8") (pin "1") (pinfunction "C_1") (pintype "passive"))
      (node (ref "JP1") (pin "V8") (pinfunction "V8_V8") (pintype "passive"))
      (node (ref "U8") (pin "2") (pinfunction "D_2") (pintype "passive"))
      (node (ref "U8") (pin "4") (pinfunction "D_4") (pintype "passive"))
    )
    (net (code "12") (name "MFC_AIN") (class "Default")
      (node (ref "JP4") (pin "3") (pinfunction "3_3") (pintype "passive"))
      (node (ref "X1") (pin "13") (pinfunction "13_13") (pintype "bidirectional"))
    )
    (net (code "13") (name "N$92") (class "Default")
      (node (ref "IC1") (pin "3") (pinfunction "+IN_3") (pintype "input"))
      (node (ref "R62") (pin "2") (pinfunction "2_2") (pintype "passive"))
    )
    (net (code "14") (name "N$A0") (class "Default")
      (node (ref "FL1") (pin "1") (pinfunction "1_1") (pintype "passive"))
      (node (ref "X1") (pin "A0") (pinfunction "A0_A0") (pintype "bidirectional"))
    )
    (net (code "15") (name "N$A1") (class "Default")
      (node (ref "FL2") (pin "1") (pinfunction "1_1") (pintype "passive"))
      (node (ref "X1") (pin "A1") (pinfunction "A1_A1") (pintype "bidirectional"))
    )
    (net (code "16") (name "N$A2") (class "Default")
      (node (ref "FL3") (pin "1") (pinfunction "1_1") (pintype "passive"))
      (node (ref "X1") (pin "A2") (pinfunction "A2_A2") (pintype "bidirectional"))
    )
    (net (code "17") (name "N$A3") (class "Default")
      (node (ref "FL4") (pin "1") (pinfunction "1_1") (pintype "passive"))
      (node (ref "X1") (pin "A3") (pinfunction "A3_A3") (pintype "bidirectional"))
    )
    (net (code "18") (name "N$A4") (class "Default")
      (node (ref "FL5") (pin "1") (pinfunction "1_1") (pintype "passive"))
      (node (ref "X1") (pin "A4") (pinfunction "A4_A4") (pintype "bidirectional"))
    )
    (net (code "19") (name "N$A5") (class "Default")
      (node (ref "FL6") (pin "1") (pinfunction "1_1") (pintype "passive"))
      (node (ref "X1") (pin "A5") (pinfunction "A5_A5") (pintype "bidirectional"))
    )
    (net (code "20") (name "N$A6") (class "Default")
      (node (ref "FL7") (pin "1") (pinfunction "1_1") (pintype "passive"))
      (node (ref "X1") (pin "A6") (pinfunction "A6_A6") (pintype "bidirectional"))
    )
    (net (code "21") (name "N$A7") (class "Default")
      (node (ref "FL8") (pin "1") (pinfunction "1_1") (pintype "passive"))
      (node (ref "X1") (pin "A7") (pinfunction "A7_A7") (pintype "bidirectional"))
    )
    (net (code "22") (name "N$A8") (class "Default")
      (node (ref "S1") (pin "5") (pinfunction "5_5") (pintype "passive"))
      (node (ref "X1") (pin "A8") (pinfunction "A8_A8") (pintype "bidirectional"))
    )
    (net (code "23") (name "N$A9") (class "Default")
      (node (ref "S1") (pin "6") (pinfunction "6_6") (pintype "passive"))
      (node (ref "X1") (pin "A9") (pinfunction "A9_A9") (pintype "bidirectional"))
    )
    (net (code "24") (name "N$A10") (class "Default")
      (node (ref "S1") (pin "7") (pinfunction "7_7") (pintype "passive"))
      (node (ref "X1") (pin "A10") (pinfunction "A10_A10") (pintype "bidirectional"))
      (node (ref "X1") (pin "A11") (pinfunction "A11_A11") (pintype "bidirectional"))
    )
    (net (code "25") (name "N$A12") (class "Default")
      (node (ref "FL9") (pin "1") (pinfunction "1_1") (pintype "passive"))
      (node (ref "X1") (pin "A12") (pinfunction "A12_A12") (pintype "bidirectional"))
    )
    (net (code "26") (name "N$A13") (class "Default")
      (node (ref "JP4") (pin "4") (pinfunction "4_4") (pintype "passive"))
      (node (ref "X1") (pin "A13") (pinfunction "A13_A13") (pintype "bidirectional"))
    )
    (net (code "27") (name "N$PV9_1") (class "Default")
      (node (ref "PV9") (pin "1") (pinfunction "1_1") (pintype "passive"))
      (node (ref "U31") (pin "2") (pinfunction "S_2") (pintype "passive"))
    )
    (net (code "28") (name "N$PV9_2") (class "Default")
      (node (ref "IC1") (pin "4") (pinfunction "-IN_4") (pintype "input"))
      (node (ref "PV9") (pin "2") (pinfunction "2_2") (pintype "passive"))
      (node (ref "R65") (pin "2") (pinfunction "2_2") (pintype "passive"))
    )
    (net (code "29") (name "N$PV9_OUT") (class "Default")
      (node (ref "IC1") (pin "1") (pinfunction "OUT_1") (pintype "output"))
      (node (ref "R66") (pin "1") (pinfunction "1_1") (pintype "passive"))
    )
    (net (code "30") (name "Net-(D9-C)") (class "Default")
      (node (ref "D9") (pin "1") (pinfunction "C_1") (pintype "passive"))
      (node (ref "J3") (pin "1") (pinfunction "1_1") (pintype "passive"))
      (node (ref "U28") (pin "2") (pinfunction "D_2") (pintype "passive"))
      (node (ref "U28") (pin "4") (pinfunction "D_4") (pintype "passive"))
    )
    (net (code "31") (name "Net-(D10-C)") (class "Default")
      (node (ref "D10") (pin "1") (pinfunction "C_1") (pintype "passive"))
      (node (ref "J4") (pin "1") (pinfunction "1_1") (pintype "passive"))
      (node (ref "U30") (pin "2") (pinfunction "D_2") (pintype "passive"))
      (node (ref "U30") (pin "4") (pinfunction "D_4") (pintype "passive"))
    )
    (net (code "32") (name "Net-(LED1-PadA)") (class "Default")
      (node (ref "LED1") (pin "A") (pinfunction "A_A") (pintype "passive"))
      (node (ref "R52") (pin "1") (pinfunction "1_1") (pintype "passive"))
    )
    (net (code "33") (name "Net-(LED2-PadA)") (class "Default")
      (node (ref "LED2") (pin "A") (pinfunction "A_A") (pintype "passive"))
      (node (ref "R53") (pin "1") (pinfunction "1_1") (pintype "passive"))
    )
    (net (code "34") (name "Net-(LED_V1-PadA)") (class "Default")
      (node (ref "LED_V1") (pin "A") (pinfunction "A_A") (pintype "passive"))
      (node (ref "R44") (pin "1") (pinfunction "1_1") (pintype "passive"))
    )
    (net (code "35") (name "Net-(LED_V2-PadA)") (class "Default")
      (node (ref "LED_V2") (pin "A") (pinfunction "A_A") (pintype "passive"))
      (node (ref "R45") (pin "1") (pinfunction "1_1") (pintype "passive"))
    )
    (net (code "36") (name "Net-(LED_V3-PadA)") (class "Default")
      (node (ref "LED_V3") (pin "A") (pinfunction "A_A") (pintype "passive"))
      (node (ref "R46") (pin "1") (pinfunction "1_1") (pintype "passive"))
    )
    (net (code "37") (name "Net-(LED_V4-PadA)") (class "Default")
      (node (ref "LED_V4") (pin "A") (pinfunction "A_A") (pintype "passive"))
      (node (ref "R47") (pin "1") (pinfunction "1_1") (pintype "passive"))
    )
    (net (code "38") (name "Net-(LED_V5-PadA)") (class "Default")
      (node (ref "LED_V5") (pin "A") (pinfunction "A_A") (pintype "passive"))
      (node (ref "R48") (pin "1") (pinfunction "1_1") (pintype "passive"))
    )
    (net (code "39") (name "Net-(LED_V6-PadA)") (class "Default")
      (node (ref "LED_V6") (pin "A") (pinfunction "A_A") (pintype "passive"))
      (node (ref "R49") (pin "1") (pinfunction "1_1") (pintype "passive"))
    )
    (net (code "40") (name "Net-(LED_V7-PadA)") (class "Default")
      (node (ref "LED_V7") (pin "A") (pinfunction "A_A") (pintype "passive"))
      (node (ref "R50") (pin "1") (pinfunction "1_1") (pintype "passive"))
    )
    (net (code "41") (name "Net-(LED_V8-PadA)") (class "Default")
      (node (ref "LED_V8") (pin "A") (pinfunction "A_A") (pintype "passive"))
      (node (ref "R51") (pin "1") (pinfunction "1_1") (pintype "passive"))
    )
    (net (code "42") (name "Net-(LED_V9-PadA)") (class "Default")
      (node (ref "LED_V9") (pin "A") (pinfunction "A_A") (pintype "passive"))
      (node (ref "R60") (pin "1") (pinfunction "1_1") (pintype "passive"))
    )
    (net (code "43") (name "Net-(LED_V10-PadA)") (class "Default")
      (node (ref "LED_V10") (pin "A") (pinfunction "A_A") (pintype "passive"))
      (node (ref "R61") (pin "1") (pinfunction "1_1") (pintype "passive"))
    )
    (net (code "44") (name "Net-(R6-Pad1)") (class "Default")
      (node (ref "R6") (pin "1") (pinfunction "1_1") (pintype "passive"))
      (node (ref "R7") (pin "1") (pinfunction "1_1") (pintype "passive"))
      (node (ref "R8") (pin "2") (pinfunction "2_2") (pintype "passive"))
    )
    (net (code "45") (name "Net-(R11-Pad1)") (class "Default")
      (node (ref "R11") (pin "1") (pinfunction "1_1") (pintype "passive"))
      (node (ref "R12") (pin "1") (pinfunction "1_1") (pintype "passive"))
      (node (ref "R13") (pin "2") (pinfunction "2_2") (pintype "passive"))
    )
    (net (code "46") (name "Net-(R14-Pad1)") (class "Default")
      (node (ref "R14") (pin "1") (pinfunction "1_1") (pintype "passive"))
      (node (ref "R15") (pin "1") (pinfunction "1_1") (pintype "passive"))
      (node (ref "R16") (pin "2") (pinfunction "2_2") (pintype "passive"))
    )
    (net (code "47") (name "Net-(R17-Pad1)") (class "Default")
      (node (ref "R17") (pin "1") (pinfunction "1_1") (pintype "passive"))
      (node (ref "R18") (pin "1") (pinfunction "1_1") (pintype "passive"))
      (node (ref "R19") (pin "2") (pinfunction "2_2") (pintype "passive"))
    )
    (net (code "48") (name "Net-(R26-Pad1)") (class "Default")
      (node (ref "R26") (pin "1") (pinfunction "1_1") (pintype "passive"))
      (node (ref "R27") (pin "1") (pinfunction "1_1") (pintype "passive"))
      (node (ref "R28") (pin "2") (pinfunction "2_2") (pintype "passive"))
    )
    (net (code "49") (name "Net-(R31-Pad1)") (class "Default")
      (node (ref "R31") (pin "1") (pinfunction "1_1") (pintype "passive"))
      (node (ref "R32") (pin "1") (pinfunction "1_1") (pintype "passive"))
      (node (ref "R33") (pin "2") (pinfunction "2_2") (pintype "passive"))
    )
    (net (code "50") (name "Net-(R34-Pad1)") (class "Default")
      (node (ref "R34") (pin "1") (pinfunction "1_1") (pintype "passive"))
      (node (ref "R35") (pin "1") (pinfunction "1_1") (pintype "passive"))
      (node (ref "R36") (pin "2") (pinfunction "2_2") (pintype "passive"))
    )
    (net (code "51") (name "Net-(R37-Pad1)") (class "Default")
      (node (ref "R37") (pin "1") (pinfunction "1_1") (pintype "passive"))
      (node (ref "R38") (pin "1") (pinfunction "1_1") (pintype "passive"))
      (node (ref "R39") (pin "2") (pinfunction "2_2") (pintype "passive"))
    )
    (net (code "52") (name "Net-(R62-Pad1)") (class "Default")
      (node (ref "R62") (pin "1") (pinfunction "1_1") (pintype "passive"))
      (node (ref "R63") (pin "1") (pinfunction "1_1") (pintype "passive"))
      (node (ref "R64") (pin "2") (pinfunction "2_2") (pintype "passive"))
    )
    (net (code "53") (name "Net-(U1-G)") (class "Default")
      (node (ref "R1") (pin "16") (pinfunction "16_16") (pintype "passive"))
      (node (ref "U1") (pin "1") (pinfunction "G_1") (pintype "passive"))
      (node (ref "U9") (pin "3") (pinfunction "D_3") (pintype "passive"))
    )
    (net (code "54") (name "Net-(U9-G)") (class "Default")
      (node (ref "R2") (pin "16") (pinfunction "16_16") (pintype "passive"))
      (node (ref "R3") (pin "16") (pinfunction "16_16") (pintype "passive"))
      (node (ref "U9") (pin "1") (pinfunction "G_1") (pintype "passive"))
    )
    (net (code "55") (name "Net-(U10-D)") (class "Default")
      (node (ref "R1") (pin "15") (pinfunction "15_15") (pintype "passive"))
      (node (ref "U10") (pin "3") (pinfunction "D_3") (pintype "passive"))
      (node (ref "U2") (pin "1") (pinfunction "G_1") (pintype "passive"))
    )
    (net (code "56") (name "Net-(U10-G)") (class "Default")
      (node (ref "R2") (pin "15") (pinfunction "15_15") (pintype "passive"))
      (node (ref "R3") (pin "15") (pinfunction "15_15") (pintype "passive"))
      (node (ref "U10") (pin "1") (pinfunction "G_1") (pintype "passive"))
    )
    (net (code "57") (name "Net-(U11-D)") (class "Default")
      (node (ref "R1") (pin "14") (pinfunction "14_14") (pintype "passive"))
      (node (ref "U11") (pin "3") (pinfunction "D_3") (pintype "passive"))
      (node (ref "U3") (pin "1") (pinfunction "G_1") (pintype "passive"))
    )
    (net (code "58") (name "Net-(U11-G)") (class "Default")
      (node (ref "R2") (pin "14") (pinfunction "14_14") (pintype "passive"))
      (node (ref "R3") (pin "14") (pinfunction "14_14") (pintype "passive"))
      (node (ref "U11") (pin "1") (pinfunction "G_1") (pintype "passive"))
    )
    (net (code "59") (name "Net-(U12-D)") (class "Default")
      (node (ref "R1") (pin "13") (pinfunction "13_13") (pintype "passive"))
      (node (ref "U12") (pin "3") (pinfunction "D_3") (pintype "passive"))
      (node (ref "U4") (pin "1") (pinfunction "G_1") (pintype "passive"))
    )
    (net (code "60") (name "Net-(U12-G)") (class "Default")
      (node (ref "R2") (pin "13") (pinfunction "13_13") (pintype "passive"))
      (node (ref "R3") (pin "13") (pinfunction "13_13") (pintype "passive"))
      (node (ref "U12") (pin "1") (pinfunction "G_1") (pintype "passive"))
    )
    (net (code "61") (name "Net-(U13-D)") (class "Default")
      (node (ref "R1") (pin "12") (pinfunction "12_12") (pintype "passive"))
      (node (ref "U13") (pin "3") (pinfunction "D_3") (pintype "passive"))
      (node (ref "U5") (pin "1") (pinfunction "G_1") (pintype "passive"))
    )
    (net (code "62") (name "Net-(U13-G)") (class "Default")
      (node (ref "R2") (pin "12") (pinfunction "12_12") (pintype "passive"))
      (node (ref "R3") (pin "12") (pinfunction "12_12") (pintype "passive"))
      (node (ref "U13") (pin "1") (pinfunction "G_1") (pintype "passive"))
    )
    (net (code "63") (name "Net-(U14-D)") (class "Default")
      (node (ref "R1") (pin "11") (pinfunction "11_11") (pintype "passive"))
      (node (ref "U14") (pin "3") (pinfunction "D_3") (pintype "passive"))
      (node (ref "U6") (pin "1") (pinfunction "G_1") (pintype "passive"))
    )
    (net (code "64") (name "Net-(U14-G)") (class "Default")
      (node (ref "R2") (pin "11") (pinfunction "11_11") (pintype "passive"))
      (node (ref "R3") (pin "11") (pinfunction "11_11") (pintype "passive"))
      (node (ref "U14") (pin "1") (pinfunction "G_1") (pintype "passive"))
    )
    (net (code "65") (name "Net-(U15-D)") (class "Default")
      (node (ref "R1") (pin "10") (pinfunction "10_10") (pintype "passive"))
      (node (ref "U15") (pin "3") (pinfunction "D_3") (pintype "passive"))
      (node (ref "U7") (pin "1") (pinfunction "G_1") (pintype "passive"))
    )
    (net (code "66") (name "Net-(U15-G)") (class "Default")
      (node (ref "R2") (pin "10") (pinfunction "10_10") (pintype "passive"))
      (node (ref "R3") (pin "10") (pinfunction "10_10") (pintype "passive"))
      (node (ref "U15") (pin "1") (pinfunction "G_1") (pintype "passive"))
    )
    (net (code "67") (name "Net-(U16-D)") (class "Default")
      (node (ref "R1") (pin "9") (pinfunction "9_9") (pintype "passive"))
      (node (ref "U16") (pin "3") (pinfunction "D_3") (pintype "passive"))
      (node (ref "U8") (pin "1") (pinfunction "G_1") (pintype "passive"))
    )
    (net (code "68") (name "Net-(U16-G)") (class "Default")
      (node (ref "R2") (pin "9") (pinfunction "9_9") (pintype "passive"))
      (node (ref "R3") (pin "9") (pinfunction "9_9") (pintype "passive"))
      (node (ref "U16") (pin "1") (pinfunction "G_1") (pintype "passive"))
    )
    (net (code "69") (name "Net-(U17-G)") (class "Default")
      (node (ref "R5") (pin "2") (pinfunction "2_2") (pintype "passive"))
      (node (ref "U17") (pin "1") (pinfunction "G_1") (pintype "passive"))
    )
    (net (code "70") (name "Net-(U17-S)") (class "Default")
      (node (ref "PV1") (pin "1") (pinfunction "1_1") (pintype "passive"))
      (node (ref "U17") (pin "2") (pinfunction "S_2") (pintype "passive"))
    )
    (net (code "71") (name "Net-(U18-G)") (class "Default")
      (node (ref "R10") (pin "2") (pinfunction "2_2") (pintype "passive"))
      (node (ref "U18") (pin "1") (pinfunction "G_1") (pintype "passive"))
    )
    (net (code "72") (name "Net-(U18-S)") (class "Default")
      (node (ref "PV2") (pin "1") (pinfunction "1_1") (pintype "passive"))
      (node (ref "U18") (pin "2") (pinfunction "S_2") (pintype "passive"))
    )
    (net (code "73") (name "Net-(U19-G)") (class "Default")
      (node (ref "R21") (pin "2") (pinfunction "2_2") (pintype "passive"))
      (node (ref "U19") (pin "1") (pinfunction "G_1") (pintype "passive"))
    )
    (net (code "74") (name "Net-(U19-S)") (class "Default")
      (node (ref "PV3") (pin "1") (pinfunction "1_1") (pintype "passive"))
      (node (ref "U19") (pin "2") (pinfunction "S_2") (pintype "passive"))
    )
    (net (code "75") (name "Net-(U20-G)") (class "Default")
      (node (ref "R23") (pin "2") (pinfunction "2_2") (pintype "passive"))
      (node (ref "U20") (pin "1") (pinfunction "G_1") (pintype "passive"))
    )
    (net (code "76") (name "Net-(U20-S)") (class "Default")
      (node (ref "PV4") (pin "1") (pinfunction "1_1") (pintype "passive"))
      (node (ref "U20") (pin "2") (pinfunction "S_2") (pintype "passive"))
    )
    (net (code "77") (name "Net-(U21-1IN+)") (class "Default")
      (node (ref "R6") (pin "2") (pinfunction "2_2") (pintype "passive"))
      (node (ref "U21") (pin "3") (pinfunction "1IN+_3") (pintype "input"))
    )
    (net (code "78") (name "Net-(U21-1IN-)") (class "Default")
      (node (ref "PV1") (pin "2") (pinfunction "2_2") (pintype "passive"))
      (node (ref "R4") (pin "2") (pinfunction "2_2") (pintype "passive"))
      (node (ref "U21") (pin "2") (pinfunction "1IN-_2") (pintype "input"))
    )
    (net (code "79") (name "Net-(U21-1OUT)") (class "Default")
      (node (ref "R5") (pin "1") (pinfunction "1_1") (pintype "passive"))
      (node (ref "U21") (pin "1") (pinfunction "1OUT_1") (pintype "output"))
    )
    (net (code "80") (name "Net-(U21-2IN+)") (class "Default")
      (node (ref "R11") (pin "2") (pinfunction "2_2") (pintype "passive"))
      (node (ref "U21") (pin "5") (pinfunction "2IN+_5") (pintype "input"))
    )
    (net (code "81") (name "Net-(U21-2IN-)") (class "Default")
      (node (ref "PV2") (pin "2") (pinfunction "2_2") (pintype "passive"))
      (node (ref "R9") (pin "2") (pinfunction "2_2") (pintype "passive"))
      (node (ref "U21") (pin "6") (pinfunction "2IN-_6") (pintype "input"))
    )
    (net (code "82") (name "Net-(U21-2OUT)") (class "Default")
      (node (ref "R10") (pin "1") (pinfunction "1_1") (pintype "passive"))
      (node (ref "U21") (pin "7") (pinfunction "2OUT_7") (pintype "output"))
    )
    (net (code "83") (name "Net-(U21-3IN+)") (class "Default")
      (node (ref "R14") (pin "2") (pinfunction "2_2") (pintype "passive"))
      (node (ref "U21") (pin "10") (pinfunction "3IN+_10") (pintype "input"))
    )
    (net (code "84") (name "Net-(U21-3IN-)") (class "Default")
      (node (ref "PV3") (pin "2") (pinfunction "2_2") (pintype "passive"))
      (node (ref "R20") (pin "2") (pinfunction "2_2") (pintype "passive"))
      (node (ref "U21") (pin "9") (pinfunction "3IN-_9") (pintype "input"))
    )
    (net (code "85") (name "Net-(U21-3OUT)") (class "Default")
      (node (ref "R21") (pin "1") (pinfunction "1_1") (pintype "passive"))
      (node (ref "U21") (pin "8") (pinfunction "3OUT_8") (pintype "output"))
    )
    (net (code "86") (name "Net-(U21-4IN+)") (class "Default")
      (node (ref "R17") (pin "2") (pinfunction "2_2") (pintype "passive"))
      (node (ref "U21") (pin "12") (pinfunction "4IN+_12") (pintype "input"))
    )
    (net (code "87") (name "Net-(U21-4IN-)") (class "Default")
      (node (ref "PV4") (pin "2") (pinfunction "2_2") (pintype "passive"))
      (node (ref "R22") (pin "2") (pinfunction "2_2") (pintype "passive"))
      (node (ref "U21") (pin "13") (pinfunction "4IN-_13") (pintype "input"))
    )
    (net (code "88") (name "Net-(U21-4OUT)") (class "Default")
      (node (ref "R23") (pin "1") (pinfunction "1_1") (pintype "passive"))
      (node (ref "U21") (pin "14") (pinfunction "4OUT_14") (pintype "output"))
    )
    (net (code "89") (name "Net-(U22-G)") (class "Default")
      (node (ref "R25") (pin "2") (pinfunction "2_2") (pintype "passive"))
      (node (ref "U22") (pin "1") (pinfunction "G_1") (pintype "passive"))
    )
    (net (code "90") (name "Net-(U22-S)") (class "Default")
      (node (ref "PV5") (pin "1") (pinfunction "1_1") (pintype "passive"))
      (node (ref "U22") (pin "2") (pinfunction "S_2") (pintype "passive"))
    )
    (net (code "91") (name "Net-(U23-G)") (class "Default")
      (node (ref "R30") (pin "2") (pinfunction "2_2") (pintype "passive"))
      (node (ref "U23") (pin "1") (pinfunction "G_1") (pintype "passive"))
    )
    (net (code "92") (name "Net-(U23-S)") (class "Default")
      (node (ref "PV6") (pin "1") (pinfunction "1_1") (pintype "passive"))
      (node (ref "U23") (pin "2") (pinfunction "S_2") (pintype "passive"))
    )
    (net (code "93") (name "Net-(U24-G)") (class "Default")
      (node (ref "R41") (pin "2") (pinfunction "2_2") (pintype "passive"))
      (node (ref "U24") (pin "1") (pinfunction "G_1") (pintype "passive"))
    )
    (net (code "94") (name "Net-(U24-S)") (class "Default")
      (node (ref "PV7") (pin "1") (pinfunction "1_1") (pintype "passive"))
      (node (ref "U24") (pin "2") (pinfunction "S_2") (pintype "passive"))
    )
    (net (code "95") (name "Net-(U25-G)") (class "Default")
      (node (ref "R43") (pin "2") (pinfunction "2_2") (pintype "passive"))
      (node (ref "U25") (pin "1") (pinfunction "G_1") (pintype "passive"))
    )
    (net (code "96") (name "Net-(U25-S)") (class "Default")
      (node (ref "PV8") (pin "1") (pinfunction "1_1") (pintype "passive"))
      (node (ref "U25") (pin "2") (pinfunction "S_2") (pintype "passive"))
    )
    (net (code "97") (name "Net-(U26-1IN+)") (class "Default")
      (node (ref "R26") (pin "2") (pinfunction "2_2") (pintype "passive"))
      (node (ref "U26") (pin "3") (pinfunction "1IN+_3") (pintype "input"))
    )
    (net (code "98") (name "Net-(U26-1IN-)") (class "Default")
      (node (ref "PV5") (pin "2") (pinfunction "2_2") (pintype "passive"))
      (node (ref "R24") (pin "2") (pinfunction "2_2") (pintype "passive"))
      (node (ref "U26") (pin "2") (pinfunction "1IN-_2") (pintype "input"))
    )
    (net (code "99") (name "Net-(U26-1OUT)") (class "Default")
      (node (ref "R25") (pin "1") (pinfunction "1_1") (pintype "passive"))
      (node (ref "U26") (pin "1") (pinfunction "1OUT_1") (pintype "output"))
    )
    (net (code "100") (name "Net-(U26-2IN+)") (class "Default")
      (node (ref "R31") (pin "2") (pinfunction "2_2") (pintype "passive"))
      (node (ref "U26") (pin "5") (pinfunction "2IN+_5") (pintype "input"))
    )
    (net (code "101") (name "Net-(U26-2IN-)") (class "Default")
      (node (ref "PV6") (pin "2") (pinfunction "2_2") (pintype "passive"))
      (node (ref "R29") (pin "2") (pinfunction "2_2") (pintype "passive"))
      (node (ref "U26") (pin "6") (pinfunction "2IN-_6") (pintype "input"))
    )
    (net (code "102") (name "Net-(U26-2OUT)") (class "Default")
      (node (ref "R30") (pin "1") (pinfunction "1_1") (pintype "passive"))
      (node (ref "U26") (pin "7") (pinfunction "2OUT_7") (pintype "output"))
    )
    (net (code "103") (name "Net-(U26-3IN+)") (class "Default")
      (node (ref "R34") (pin "2") (pinfunction "2_2") (pintype "passive"))
      (node (ref "U26") (pin "10") (pinfunction "3IN+_10") (pintype "input"))
    )
    (net (code "104") (name "Net-(U26-3IN-)") (class "Default")
      (node (ref "PV7") (pin "2") (pinfunction "2_2") (pintype "passive"))
      (node (ref "R40") (pin "2") (pinfunction "2_2") (pintype "passive"))
      (node (ref "U26") (pin "9") (pinfunction "3IN-_9") (pintype "input"))
    )
    (net (code "105") (name "Net-(U26-3OUT)") (class "Default")
      (node (ref "R41") (pin "1") (pinfunction "1_1") (pintype "passive"))
      (node (ref "U26") (pin "8") (pinfunction "3OUT_8") (pintype "output"))
    )
    (net (code "106") (name "Net-(U26-4IN+)") (class "Default")
      (node (ref "R37") (pin "2") (pinfunction "2_2") (pintype "passive"))
      (node (ref "U26") (pin "12") (pinfunction "4IN+_12") (pintype "input"))
    )
    (net (code "107") (name "Net-(U26-4IN-)") (class "Default")
      (node (ref "PV8") (pin "2") (pinfunction "2_2") (pintype "passive"))
      (node (ref "R42") (pin "2") (pinfunction "2_2") (pintype "passive"))
      (node (ref "U26") (pin "13") (pinfunction "4IN-_13") (pintype "input"))
    )
    (net (code "108") (name "Net-(U26-4OUT)") (class "Default")
      (node (ref "R43") (pin "1") (pinfunction "1_1") (pintype "passive"))
      (node (ref "U26") (pin "14") (pinfunction "4OUT_14") (pintype "output"))
    )
    (net (code "109") (name "Net-(U27-D)") (class "Default")
      (node (ref "R56") (pin "1") (pinfunction "1_1") (pintype "passive"))
      (node (ref "U27") (pin "3") (pinfunction "D_3") (pintype "passive"))
      (node (ref "U28") (pin "1") (pinfunction "G_1") (pintype "passive"))
    )
    (net (code "110") (name "Net-(U27-G)") (class "Default")
      (node (ref "R54") (pin "2") (pinfunction "2_2") (pintype "passive"))
      (node (ref "R55") (pin "2") (pinfunction "2_2") (pintype "passive"))
      (node (ref "U27") (pin "1") (pinfunction "G_1") (pintype "passive"))
    )
    (net (code "111") (name "Net-(U29-D)") (class "Default")
      (node (ref "R59") (pin "1") (pinfunction "1_1") (pintype "passive"))
      (node (ref "U29") (pin "3") (pinfunction "D_3") (pintype "passive"))
      (node (ref "U30") (pin "1") (pinfunction "G_1") (pintype "passive"))
    )
    (net (code "112") (name "Net-(U29-G)") (class "Default")
      (node (ref "R57") (pin "2") (pinfunction "2_2") (pintype "passive"))
      (node (ref "R58") (pin "2") (pinfunction "2_2") (pintype "passive"))
      (node (ref "U29") (pin "1") (pinfunction "G_1") (pintype "passive"))
    )
    (net (code "113") (name "Net-(U31-G)") (class "Default")
      (node (ref "R66") (pin "2") (pinfunction "2_2") (pintype "passive"))
      (node (ref "U31") (pin "1") (pinfunction "G_1") (pintype "passive"))
    )
    (net (code "114") (name "P1") (class "Default")
      (node (ref "R7") (pin "2") (pinfunction "2_2") (pintype "passive"))
      (node (ref "X1") (pin "2") (pinfunction "2_2") (pintype "bidirectional"))
    )
    (net (code "115") (name "P2") (class "Default")
      (node (ref "R12") (pin "2") (pinfunction "2_2") (pintype "passive"))
      (node (ref "X1") (pin "3") (pinfunction "3_3") (pintype "bidirectional"))
    )
    (net (code "116") (name "P3") (class "Default")
      (node (ref "R15") (pin "2") (pinfunction "2_2") (pintype "passive"))
      (node (ref "X1") (pin "4") (pinfunction "4_4") (pintype "bidirectional"))
    )
    (net (code "117") (name "P4") (class "Default")
      (node (ref "R18") (pin "2") (pinfunction "2_2") (pintype "passive"))
      (node (ref "X1") (pin "5") (pinfunction "5_5") (pintype "bidirectional"))
    )
    (net (code "118") (name "P5") (class "Default")
      (node (ref "R27") (pin "2") (pinfunction "2_2") (pintype "passive"))
      (node (ref "X1") (pin "6") (pinfunction "6_6") (pintype "bidirectional"))
    )
    (net (code "119") (name "P6") (class "Default")
      (node (ref "R32") (pin "2") (pinfunction "2_2") (pintype "passive"))
      (node (ref "X1") (pin "7") (pinfunction "7_7") (pintype "bidirectional"))
    )
    (net (code "120") (name "P7") (class "Default")
      (node (ref "R35") (pin "2") (pinfunction "2_2") (pintype "passive"))
      (node (ref "X1") (pin "8") (pinfunction "8_8") (pintype "bidirectional"))
    )
    (net (code "121") (name "P8") (class "Default")
      (node (ref "R38") (pin "2") (pinfunction "2_2") (pintype "passive"))
      (node (ref "X1") (pin "9") (pinfunction "9_9") (pintype "bidirectional"))
    )
    (net (code "122") (name "P9") (class "Default")
      (node (ref "R63") (pin "2") (pinfunction "2_2") (pintype "passive"))
      (node (ref "X1") (pin "10") (pinfunction "10_10") (pintype "bidirectional"))
    )
    (net (code "123") (name "SCL") (class "Default")
      (node (ref "J2") (pin "4") (pinfunction "4_4") (pintype "passive"))
      (node (ref "JP2") (pin "5") (pinfunction "5_5") (pintype "passive"))
      (node (ref "JP3") (pin "5") (pinfunction "5_5") (pintype "passive"))
      (node (ref "X1") (pin "21") (pinfunction "21(SCL)_21") (pintype "bidirectional"))
    )
    (net (code "124") (name "SDA") (class "Default")
      (node (ref "J2") (pin "2") (pinfunction "2_2") (pintype "passive"))
      (node (ref "JP2") (pin "1") (pinfunction "1_1") (pintype "passive"))
      (node (ref "JP3") (pin "1") (pinfunction "1_1") (pintype "passive"))
      (node (ref "X1") (pin "20") (pinfunction "20(SDA)_20") (pintype "bidirectional"))
    )
    (net (code "125") (name "V1") (class "Default")
      (node (ref "R3") (pin "1") (pinfunction "1_1") (pintype "passive"))
      (node (ref "R44") (pin "2") (pinfunction "2_2") (pintype "passive"))
      (node (ref "X1") (pin "22") (pinfunction "22_22") (pintype "bidirectional"))
    )
    (net (code "126") (name "V2") (class "Default")
      (node (ref "R3") (pin "2") (pinfunction "2_2") (pintype "passive"))
      (node (ref "R45") (pin "2") (pinfunction "2_2") (pintype "passive"))
      (node (ref "X1") (pin "23") (pinfunction "23_23") (pintype "bidirectional"))
    )
    (net (code "127") (name "V3") (class "Default")
      (node (ref "R3") (pin "3") (pinfunction "3_3") (pintype "passive"))
      (node (ref "R46") (pin "2") (pinfunction "2_2") (pintype "passive"))
      (node (ref "X1") (pin "24") (pinfunction "24_24") (pintype "bidirectional"))
    )
    (net (code "128") (name "V4") (class "Default")
      (node (ref "R3") (pin "4") (pinfunction "4_4") (pintype "passive"))
      (node (ref "R47") (pin "2") (pinfunction "2_2") (pintype "passive"))
      (node (ref "X1") (pin "25") (pinfunction "25_25") (pintype "bidirectional"))
    )
    (net (code "129") (name "V5") (class "Default")
      (node (ref "R3") (pin "5") (pinfunction "5_5") (pintype "passive"))
      (node (ref "R48") (pin "2") (pinfunction "2_2") (pintype "passive"))
      (node (ref "X1") (pin "26") (pinfunction "26_26") (pintype "bidirectional"))
    )
    (net (code "130") (name "V6") (class "Default")
      (node (ref "R3") (pin "6") (pinfunction "6_6") (pintype "passive"))
      (node (ref "R49") (pin "2") (pinfunction "2_2") (pintype "passive"))
      (node (ref "X1") (pin "27") (pinfunction "27_27") (pintype "bidirectional"))
    )
    (net (code "131") (name "V7") (class "Default")
      (node (ref "R3") (pin "7") (pinfunction "7_7") (pintype "passive"))
      (node (ref "R50") (pin "2") (pinfunction "2_2") (pintype "passive"))
      (node (ref "X1") (pin "28") (pinfunction "28_28") (pintype "bidirectional"))
    )
    (net (code "132") (name "V8") (class "Default")
      (node (ref "R3") (pin "8") (pinfunction "8_8") (pintype "passive"))
      (node (ref "R51") (pin "2") (pinfunction "2_2") (pintype "passive"))
      (node (ref "X1") (pin "29") (pinfunction "29_29") (pintype "bidirectional"))
    )
    (net (code "133") (name "V9") (class "Default")
      (node (ref "R54") (pin "1") (pinfunction "1_1") (pintype "passive"))
      (node (ref "R60") (pin "2") (pinfunction "2_2") (pintype "passive"))
      (node (ref "X1") (pin "30") (pinfunction "30_30") (pintype "bidirectional"))
    )
    (net (code "134") (name "V10") (class "Default")
      (node (ref "R57") (pin "1") (pinfunction "1_1") (pintype "passive"))
      (node (ref "R61") (pin "2") (pinfunction "2_2") (pintype "passive"))
      (node (ref "X1") (pin "31") (pinfunction "31_31") (pintype "bidirectional"))
    )
    (net (code "135") (name "unconnected-(JP4-Pad5)") (class "Default")
      (node (ref "JP4") (pin "5") (pinfunction "5_5") (pintype "passive"))
    )
    (net (code "136") (name "unconnected-(JP4-Pad6)") (class "Default")
      (node (ref "JP4") (pin "6") (pinfunction "6_6") (pintype "passive"))
    )
    (net (code "137") (name "unconnected-(S1-Pad8)") (class "Default")
      (node (ref "S1") (pin "8") (pinfunction "8_8") (pintype "passive"))
    )
    (net (code "138") (name "unconnected-(X1-PadA14)") (class "Default")
      (node (ref "X1") (pin "A14") (pinfunction "A14_A14") (pintype "bidirectional"))
    )
    (net (code "139") (name "unconnected-(X1-PadA15)") (class "Default")
      (node (ref "X1") (pin "A15") (pinfunction "A15_A15") (pintype "bidirectional"))
    )
  )
)
